# cnc-controller.net
KiCad netlist of a schematic drawn in EAGLE
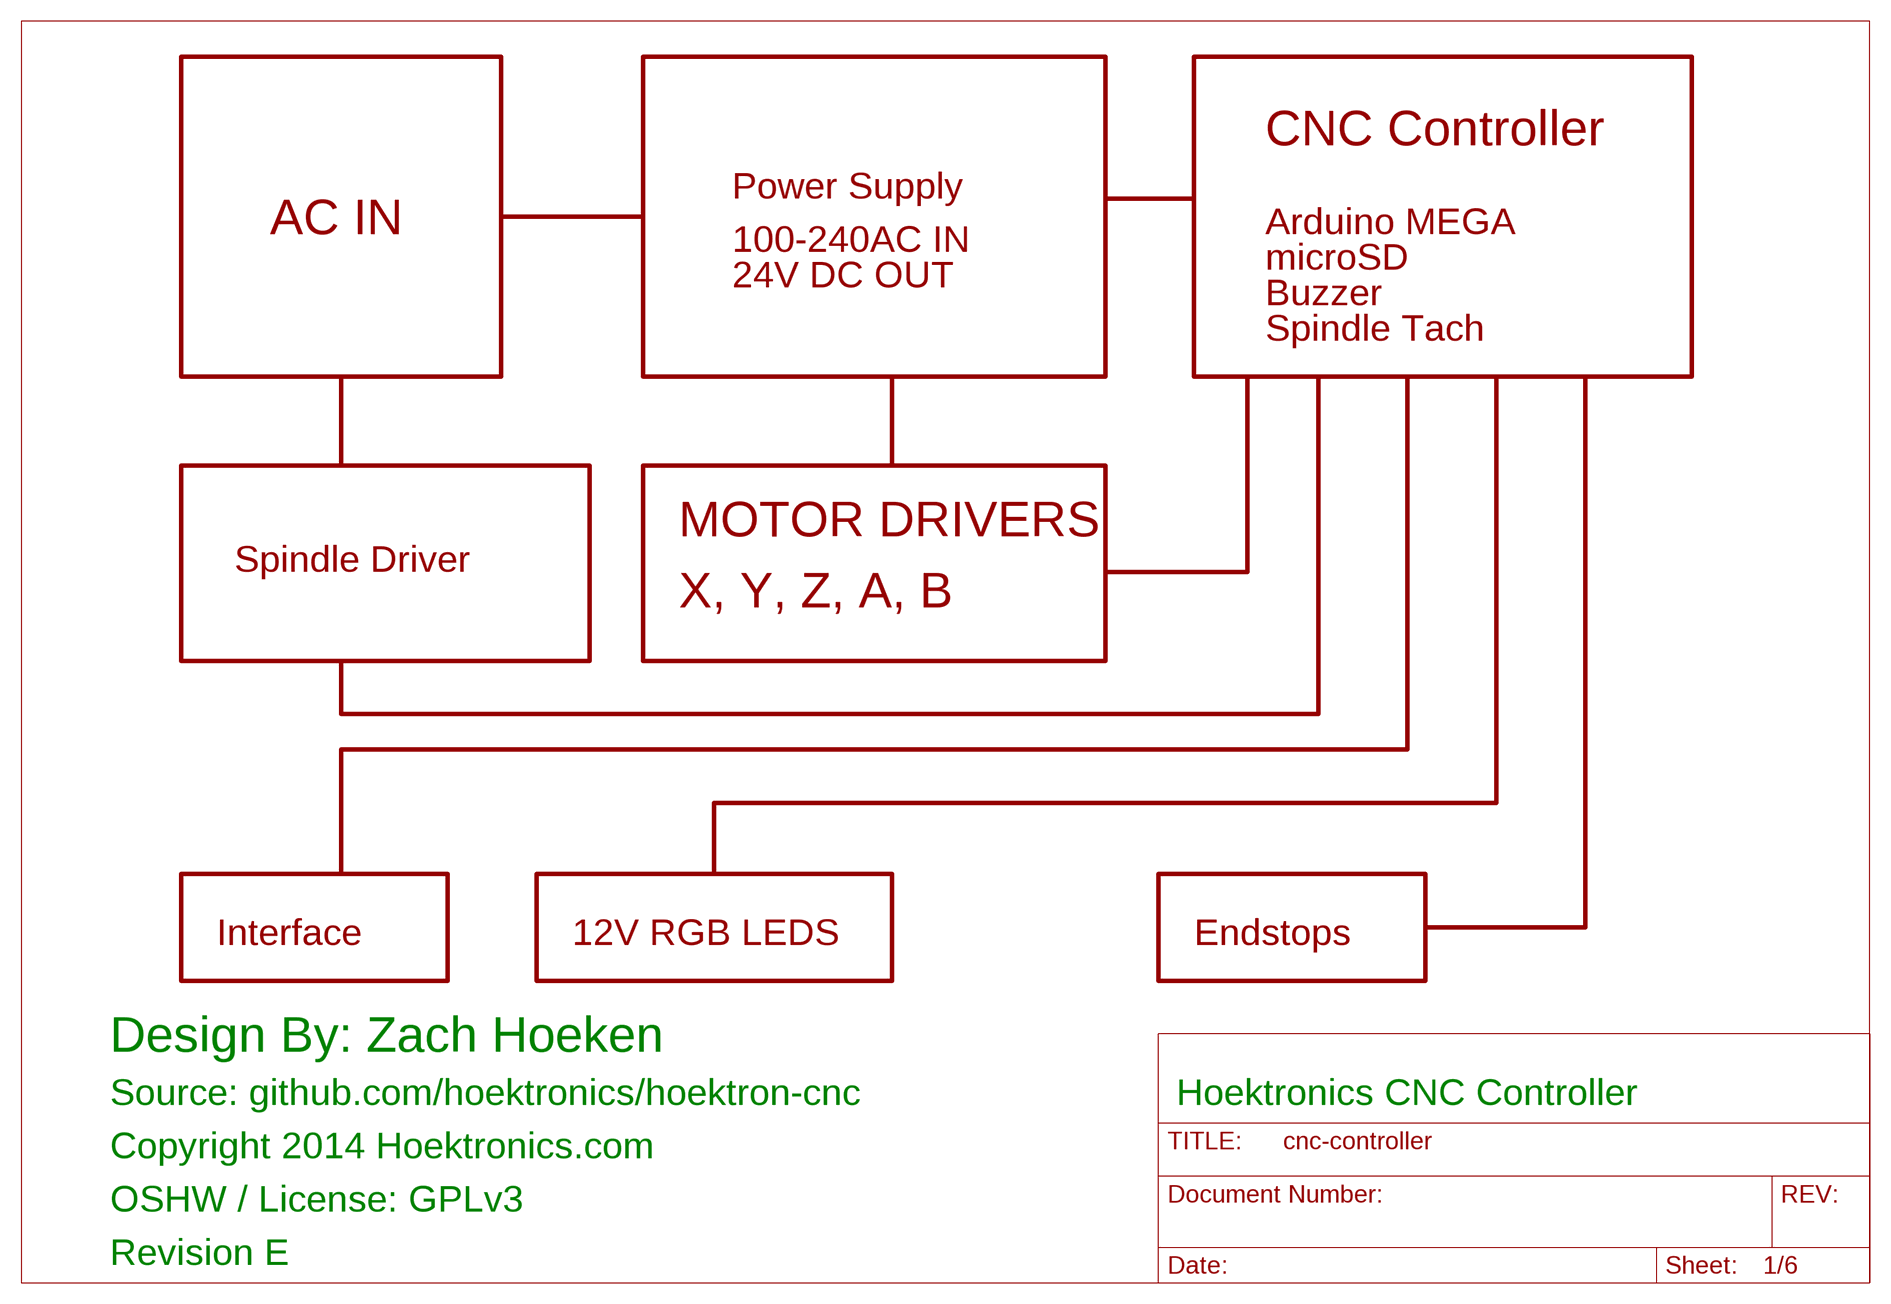
[diagram p0: schematic, sheet 1]
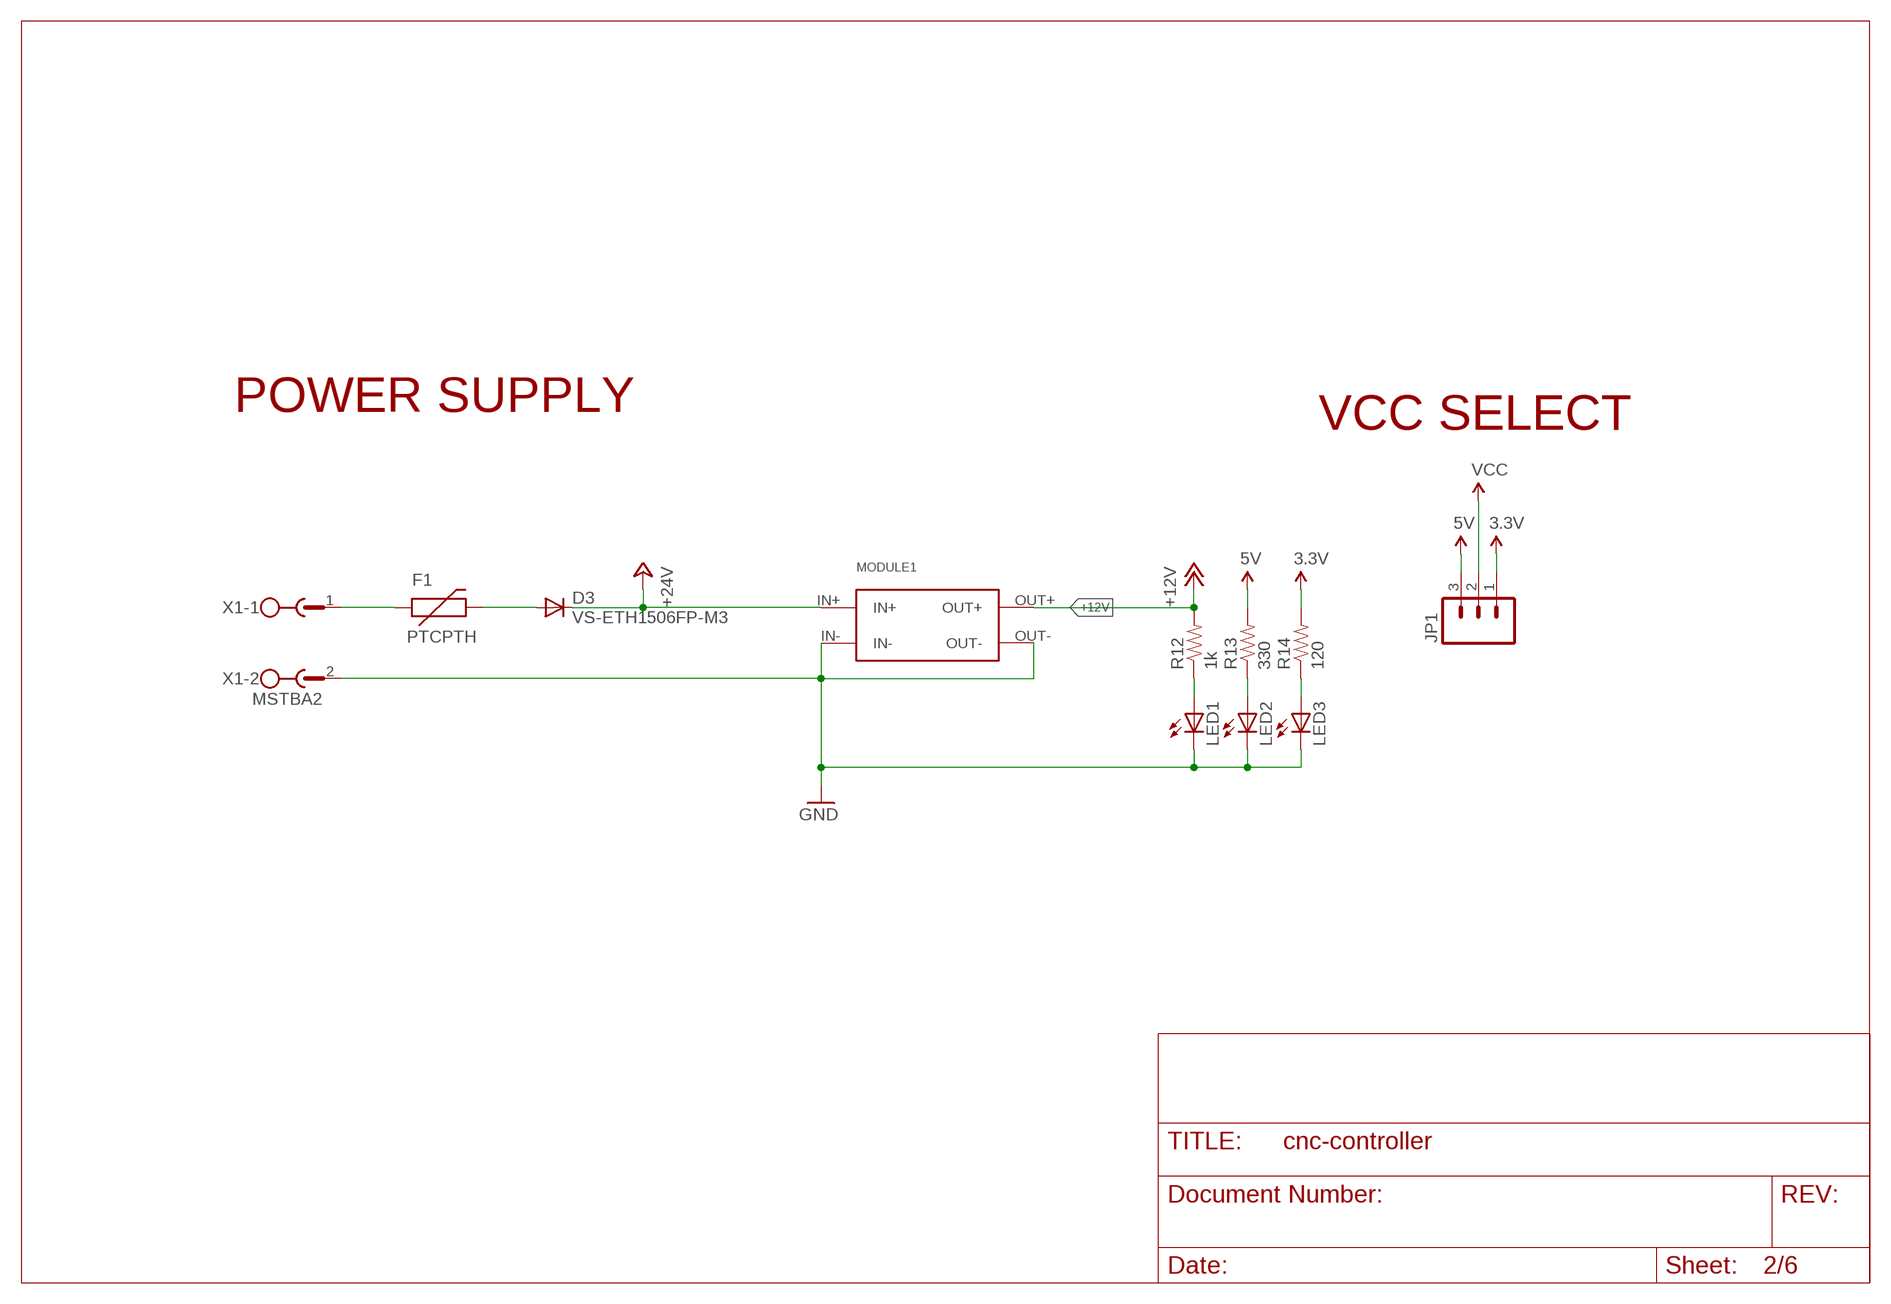
[diagram p1: schematic, sheet 2]
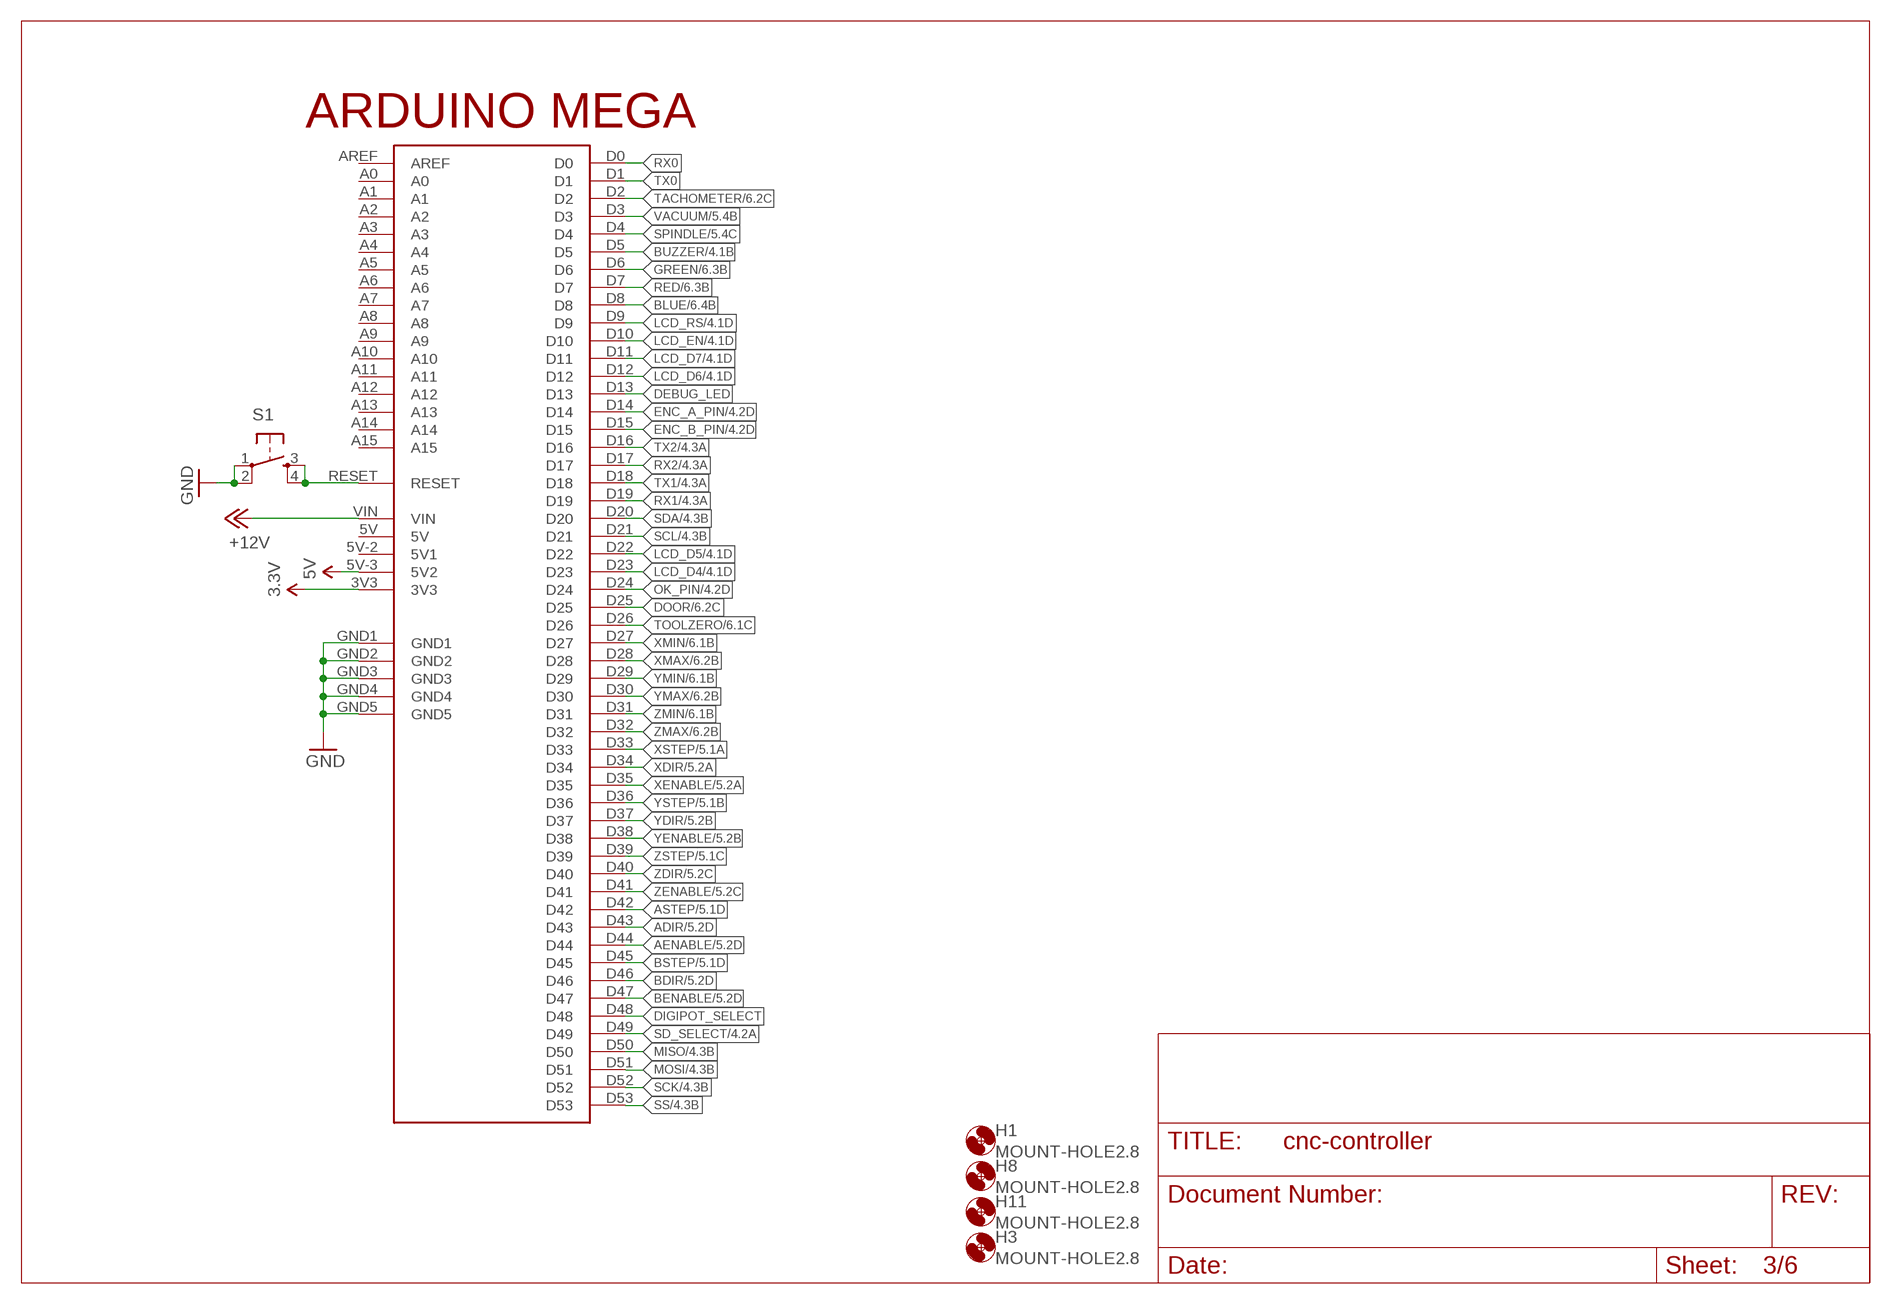
[diagram p2: schematic, sheet 3]
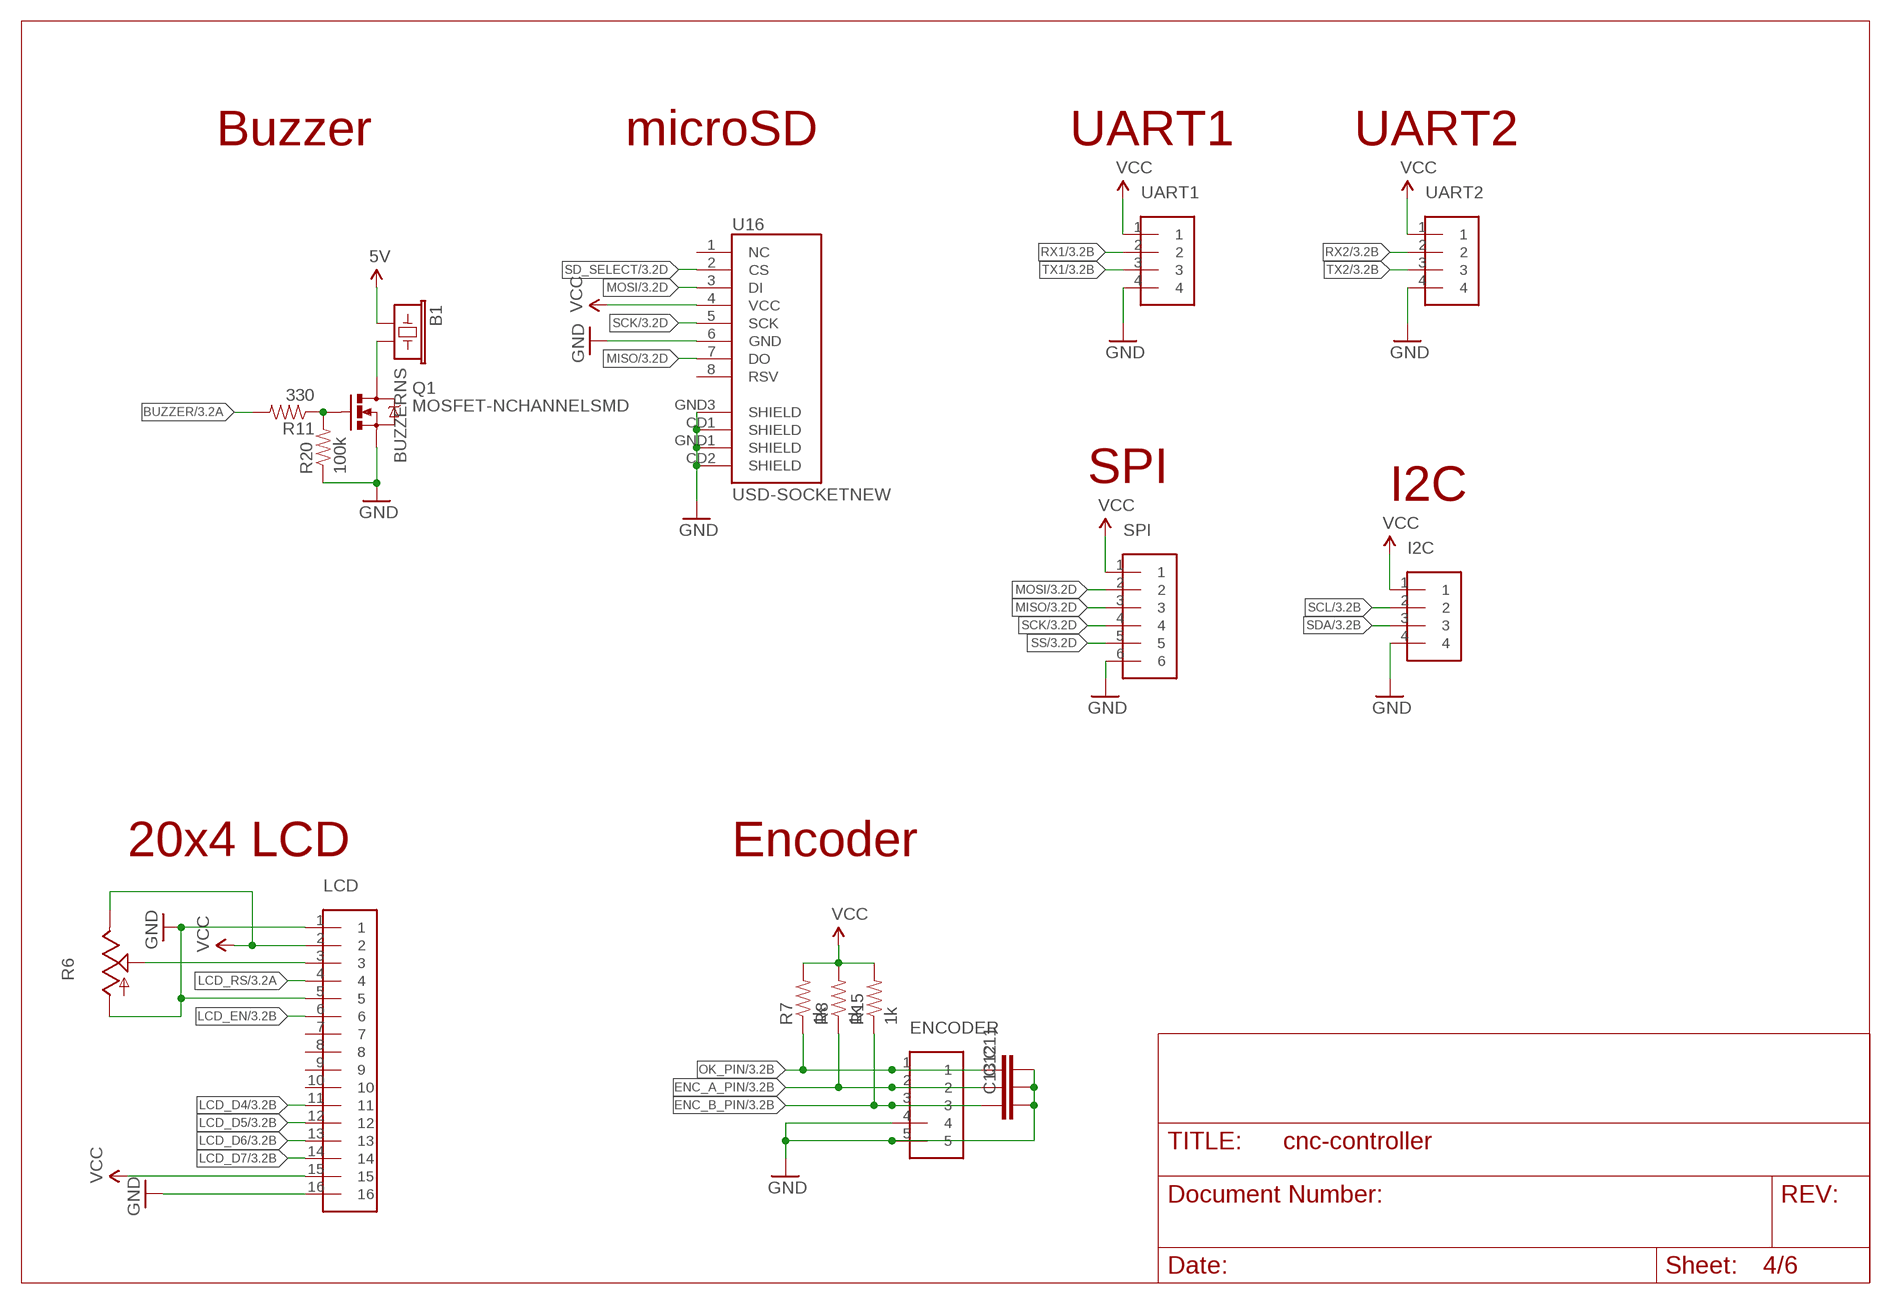
[diagram p3: schematic, sheet 4]
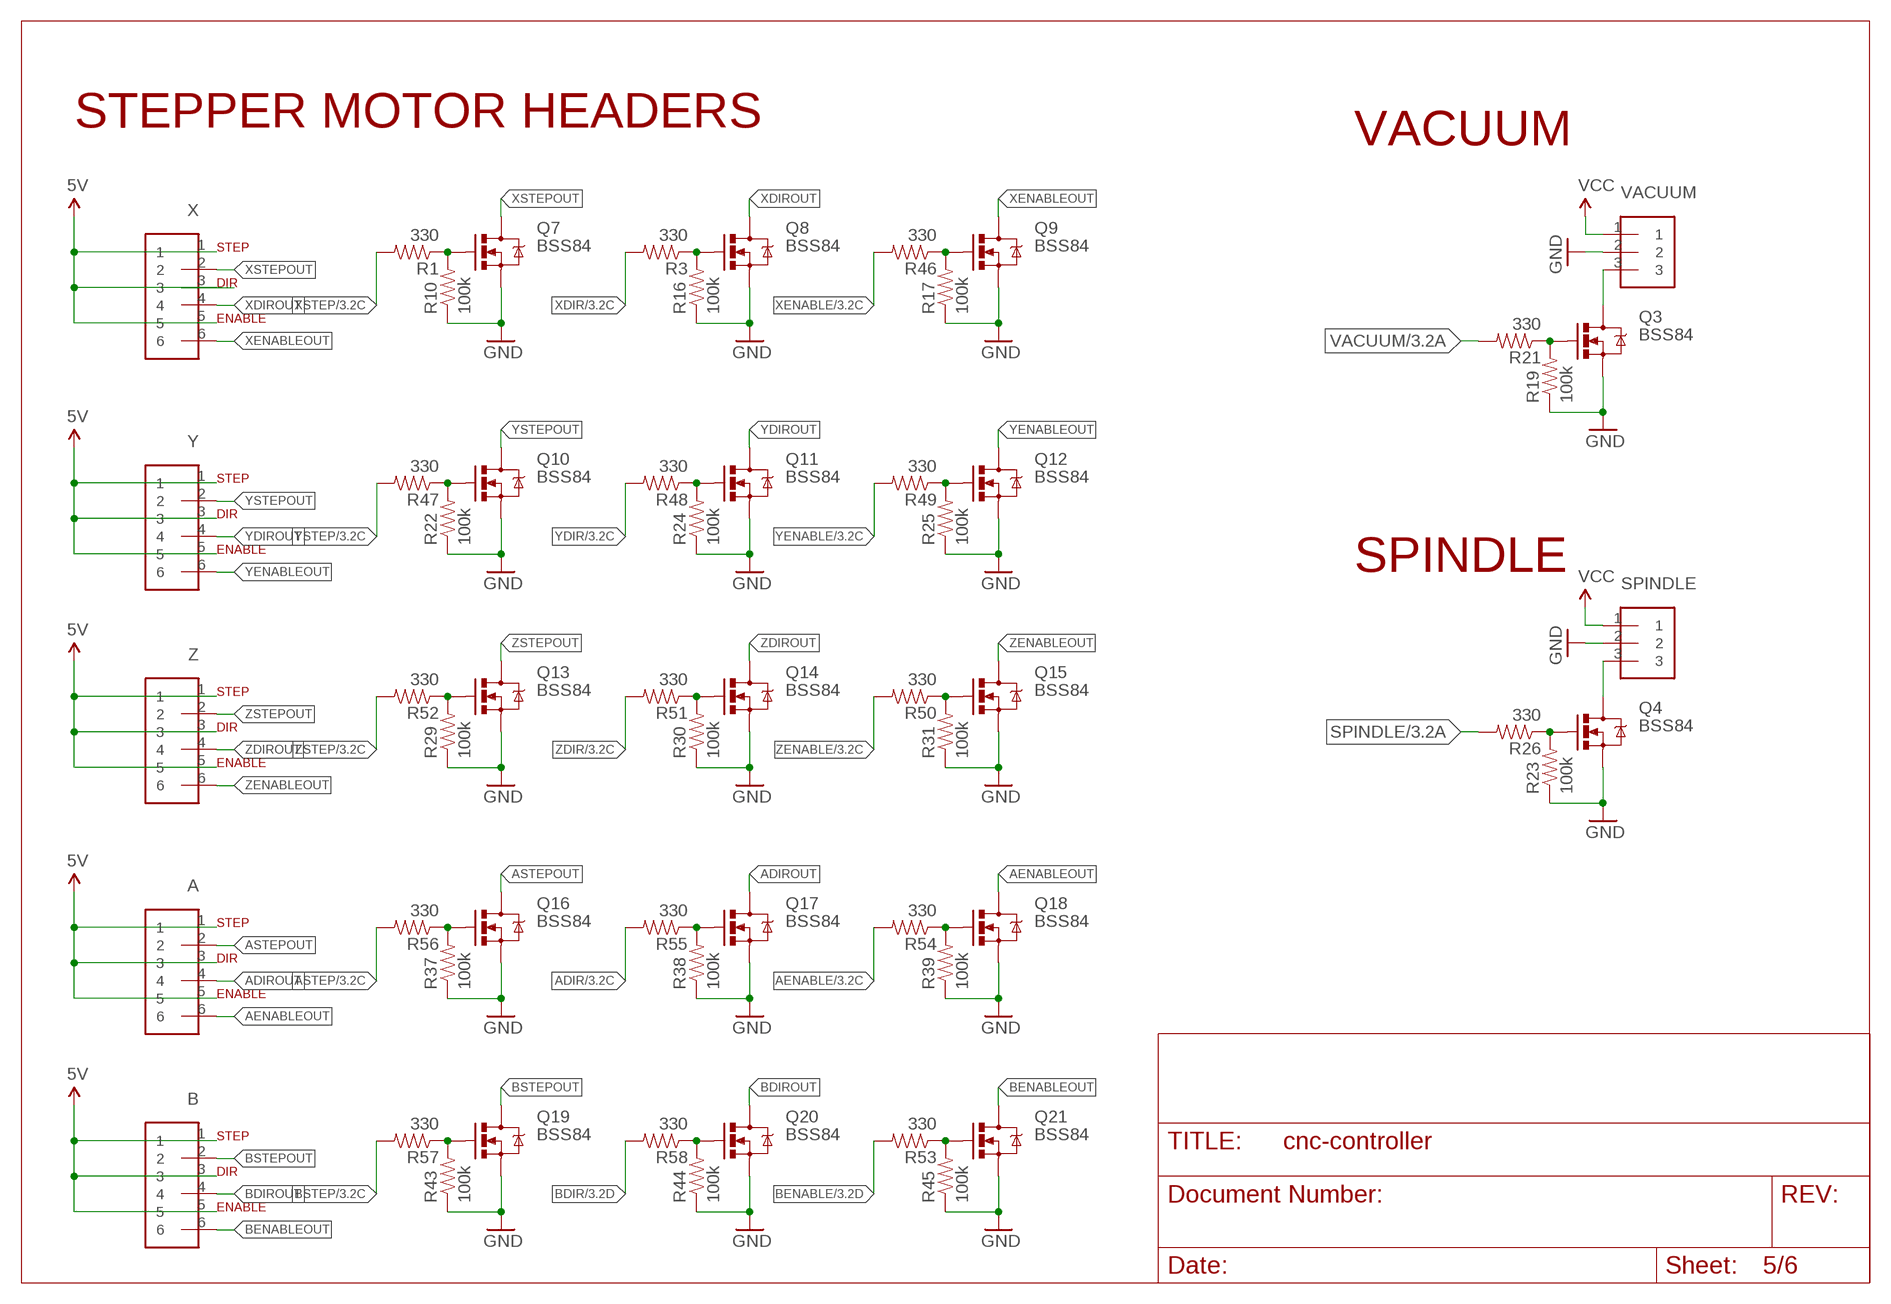
[diagram p4: schematic, sheet 5]
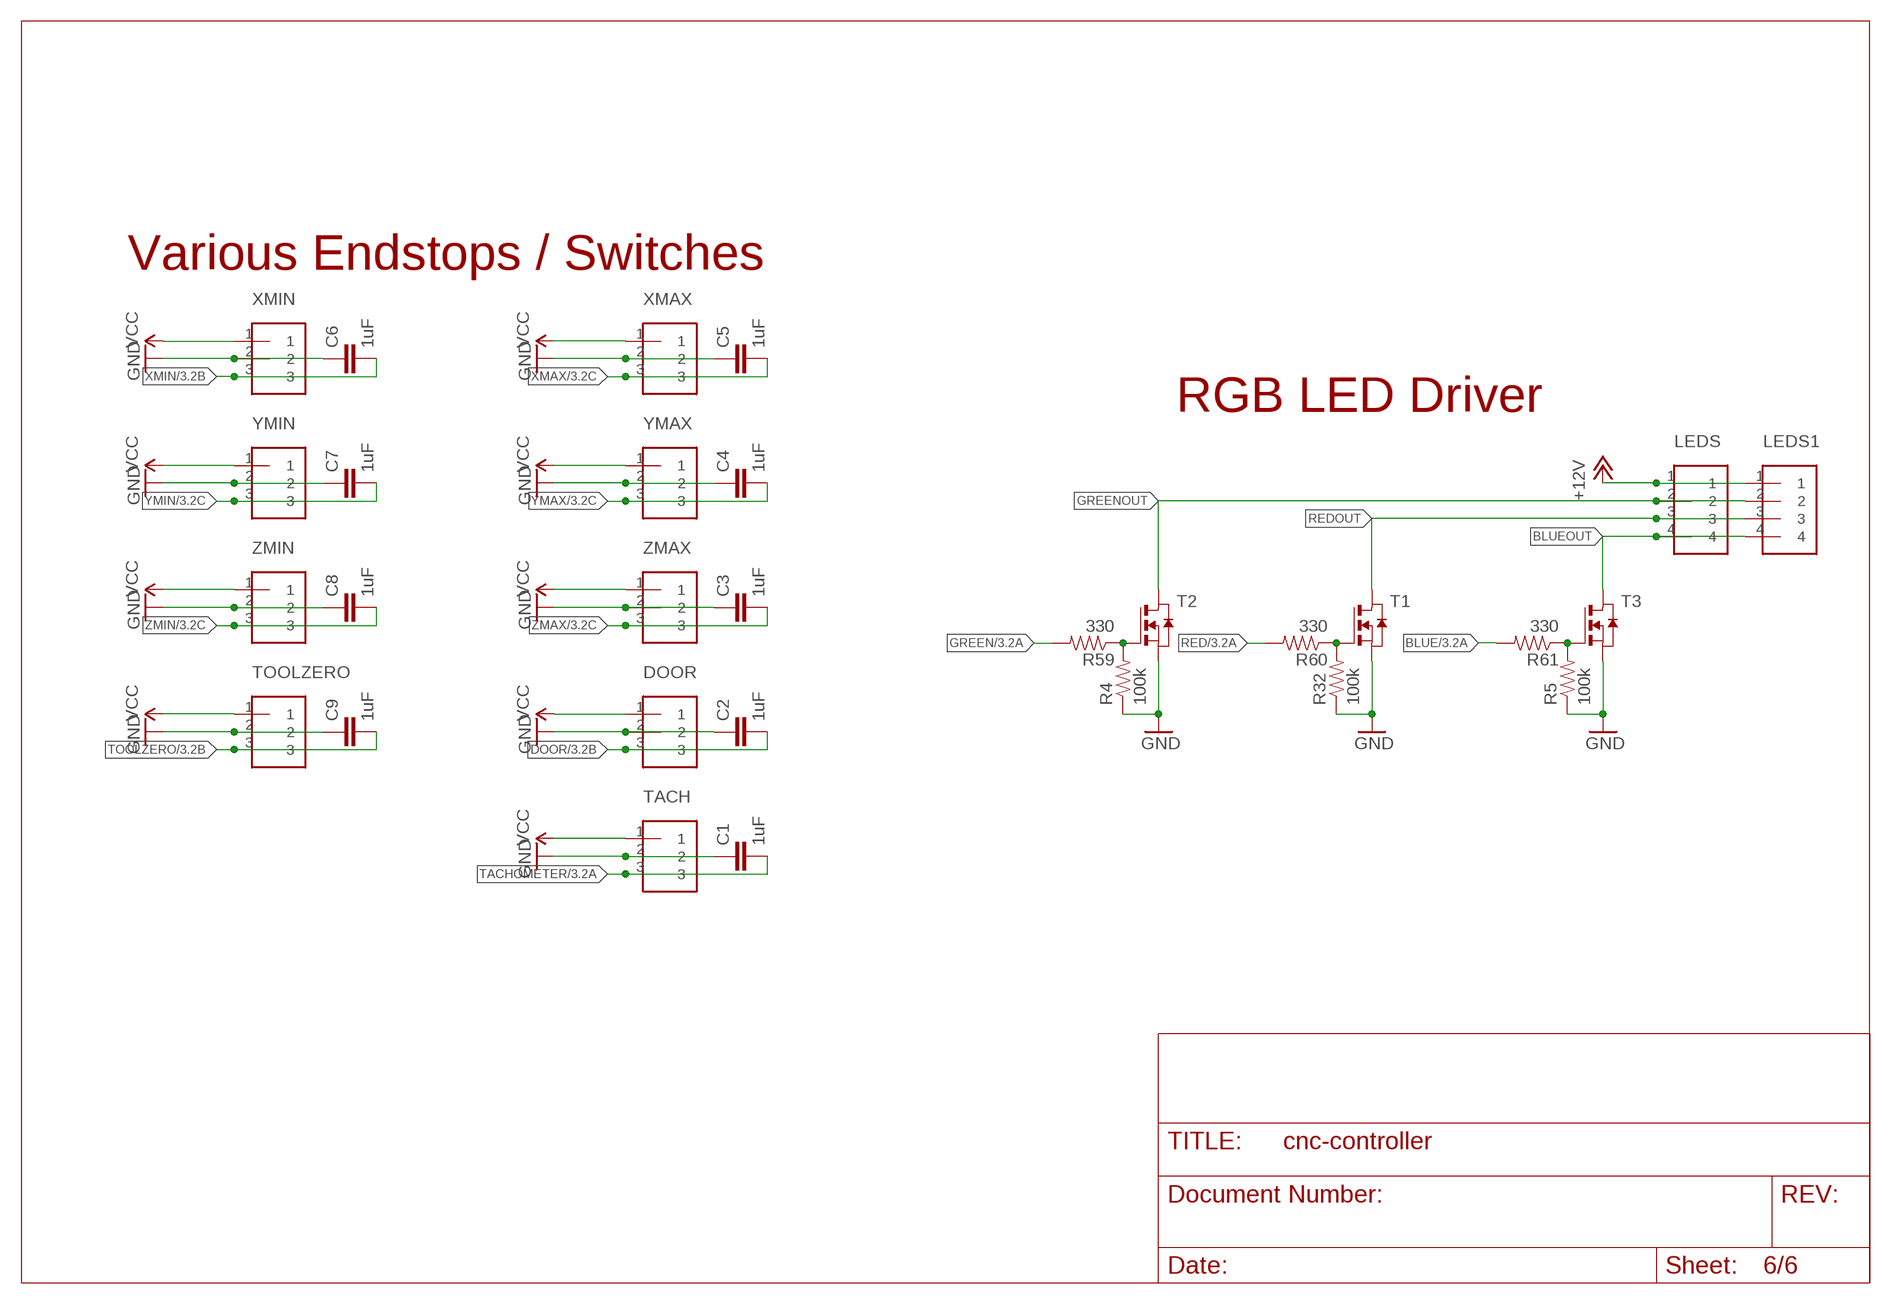
[diagram p5: schematic, sheet 6]

(export (version "E")
  (design (tool "Eeschema 10.0.6"))
  (components
    (comp (ref "C1")
      (value "1uF")
      (footprint "eagle-import:0603-RC")
      (libsource (lib "eagle-import") (part "CAPACITOR0603"))
    )
    (comp (ref "C2")
      (value "1uF")
      (footprint "eagle-import:0603-RC")
      (libsource (lib "eagle-import") (part "CAPACITOR0603"))
    )
    (comp (ref "C3")
      (value "1uF")
      (footprint "eagle-import:0603-RC")
      (libsource (lib "eagle-import") (part "CAPACITOR0603"))
    )
    (comp (ref "C4")
      (value "1uF")
      (footprint "eagle-import:0603-RC")
      (libsource (lib "eagle-import") (part "CAPACITOR0603"))
    )
    (comp (ref "C5")
      (value "1uF")
      (footprint "eagle-import:0603-RC")
      (libsource (lib "eagle-import") (part "CAPACITOR0603"))
    )
    (comp (ref "C6")
      (value "1uF")
      (footprint "eagle-import:0603-RC")
      (libsource (lib "eagle-import") (part "CAPACITOR0603"))
    )
    (comp (ref "C7")
      (value "1uF")
      (footprint "eagle-import:0603-RC")
      (libsource (lib "eagle-import") (part "CAPACITOR0603"))
    )
    (comp (ref "C8")
      (value "1uF")
      (footprint "eagle-import:0603-RC")
      (libsource (lib "eagle-import") (part "CAPACITOR0603"))
    )
    (comp (ref "C9")
      (value "1uF")
      (footprint "eagle-import:0603-RC")
      (libsource (lib "eagle-import") (part "CAPACITOR0603"))
    )
    (comp (ref "DOOR")
      (value "CONN-3XH-3")
      (footprint "eagle-import:XH-3")
      (libsource (lib "eagle-import") (part "CONN-3XH-3"))
    )
    (comp (ref "LEDS")
      (value "CONN-4")
      (footprint "eagle-import:XH-4")
      (libsource (lib "eagle-import") (part "CONN-4"))
    )
    (comp (ref "LEDS1")
      (value "CONN-4")
      (footprint "eagle-import:XH-4")
      (libsource (lib "eagle-import") (part "CONN-4"))
    )
    (comp (ref "R4")
      (value "100k")
      (footprint "eagle-import:0603-RC")
      (libsource (lib "eagle-import") (part "RESISTOR0603"))
    )
    (comp (ref "R5")
      (value "100k")
      (footprint "eagle-import:0603-RC")
      (libsource (lib "eagle-import") (part "RESISTOR0603"))
    )
    (comp (ref "R32")
      (value "100k")
      (footprint "eagle-import:0603-RC")
      (libsource (lib "eagle-import") (part "RESISTOR0603"))
    )
    (comp (ref "R59")
      (value "330")
      (footprint "eagle-import:0603-RC")
      (libsource (lib "eagle-import") (part "RESISTOR0603"))
    )
    (comp (ref "R60")
      (value "330")
      (footprint "eagle-import:0603-RC")
      (libsource (lib "eagle-import") (part "RESISTOR0603"))
    )
    (comp (ref "R61")
      (value "330")
      (footprint "eagle-import:0603-RC")
      (libsource (lib "eagle-import") (part "RESISTOR0603"))
    )
    (comp (ref "T1")
      (value "NMOSSOT89")
      (footprint "eagle-import:SOT89")
      (libsource (lib "eagle-import") (part "NMOSSOT89"))
    )
    (comp (ref "T2")
      (value "NMOSSOT89")
      (footprint "eagle-import:SOT89")
      (libsource (lib "eagle-import") (part "NMOSSOT89"))
    )
    (comp (ref "T3")
      (value "NMOSSOT89")
      (footprint "eagle-import:SOT89")
      (libsource (lib "eagle-import") (part "NMOSSOT89"))
    )
    (comp (ref "TACH")
      (value "CONN-3XH-3")
      (footprint "eagle-import:XH-3")
      (libsource (lib "eagle-import") (part "CONN-3XH-3"))
    )
    (comp (ref "TOOLZERO")
      (value "CONN-3XH-3")
      (footprint "eagle-import:XH-3")
      (libsource (lib "eagle-import") (part "CONN-3XH-3"))
    )
    (comp (ref "XMAX")
      (value "CONN-3XH-3")
      (footprint "eagle-import:XH-3")
      (libsource (lib "eagle-import") (part "CONN-3XH-3"))
    )
    (comp (ref "XMIN")
      (value "CONN-3XH-3")
      (footprint "eagle-import:XH-3")
      (libsource (lib "eagle-import") (part "CONN-3XH-3"))
    )
    (comp (ref "YMAX")
      (value "CONN-3XH-3")
      (footprint "eagle-import:XH-3")
      (libsource (lib "eagle-import") (part "CONN-3XH-3"))
    )
    (comp (ref "YMIN")
      (value "CONN-3XH-3")
      (footprint "eagle-import:XH-3")
      (libsource (lib "eagle-import") (part "CONN-3XH-3"))
    )
    (comp (ref "ZMAX")
      (value "CONN-3XH-3")
      (footprint "eagle-import:XH-3")
      (libsource (lib "eagle-import") (part "CONN-3XH-3"))
    )
    (comp (ref "ZMIN")
      (value "CONN-3XH-3")
      (footprint "eagle-import:XH-3")
      (libsource (lib "eagle-import") (part "CONN-3XH-3"))
    )
    (comp (ref "H1")
      (value "MOUNT-HOLE2.8")
      (footprint "eagle-import:2,8")
      (libsource (lib "eagle-import") (part "MOUNT-HOLE2.8"))
    )
    (comp (ref "H3")
      (value "MOUNT-HOLE2.8")
      (footprint "eagle-import:2,8")
      (libsource (lib "eagle-import") (part "MOUNT-HOLE2.8"))
    )
    (comp (ref "H8")
      (value "MOUNT-HOLE2.8")
      (footprint "eagle-import:2,8")
      (libsource (lib "eagle-import") (part "MOUNT-HOLE2.8"))
    )
    (comp (ref "H11")
      (value "MOUNT-HOLE2.8")
      (footprint "eagle-import:2,8")
      (libsource (lib "eagle-import") (part "MOUNT-HOLE2.8"))
    )
    (comp (ref "S1")
      (value "TAC_SWITCHSMD")
      (footprint "eagle-import:TACTILE_SWITCH_SMD")
      (libsource (lib "eagle-import") (part "TAC_SWITCHSMD"))
    )
    (comp (ref "U$1")
      (value "ARDUINO-MEGA")
      (footprint "eagle-import:ARDUINO-MEGA")
      (libsource (lib "eagle-import") (part "ARDUINO-MEGA"))
    )
    (comp (ref "D3")
      (value "VS-ETH1506FP-M3")
      (footprint "eagle-import:SMB")
      (libsource (lib "eagle-import") (part "DIODE-SMB"))
    )
    (comp (ref "F1")
      (value "PTCPTH")
      (footprint "eagle-import:PTC")
      (libsource (lib "eagle-import") (part "PTCPTH"))
    )
    (comp (ref "JP1")
      (value "M03PTH")
      (footprint "eagle-import:1X03")
      (libsource (lib "eagle-import") (part "M03PTH"))
    )
    (comp (ref "LED1")
      (value "LED0805")
      (footprint "eagle-import:0805-LED")
      (libsource (lib "eagle-import") (part "LED0805"))
    )
    (comp (ref "LED2")
      (value "LED0805")
      (footprint "eagle-import:0805-LED")
      (libsource (lib "eagle-import") (part "LED0805"))
    )
    (comp (ref "LED3")
      (value "LED0805")
      (footprint "eagle-import:0805-LED")
      (libsource (lib "eagle-import") (part "LED0805"))
    )
    (comp (ref "MODULE1")
      (value "DC-DC-CONVERTER")
      (footprint "eagle-import:DC-DC-MODULE")
      (libsource (lib "eagle-import") (part "DC-DC-CONVERTER"))
    )
    (comp (ref "R12")
      (value "1k")
      (footprint "eagle-import:0603-RC")
      (libsource (lib "eagle-import") (part "RESISTOR0603"))
    )
    (comp (ref "R13")
      (value "330")
      (footprint "eagle-import:0603-RC")
      (libsource (lib "eagle-import") (part "RESISTOR0603"))
    )
    (comp (ref "R14")
      (value "120")
      (footprint "eagle-import:0603-RC")
      (libsource (lib "eagle-import") (part "RESISTOR0603"))
    )
    (comp (ref "X1")
      (value "MSTBA2")
      (footprint "eagle-import:MSTBA2")
      (fields (field (name "MF") "FARNELL") (field (name "MPN") "1757242"))
      (libsource (lib "eagle-import") (part "MSTBA2"))
    )
    (comp (ref "A")
      (value "CONN-6")
      (footprint "eagle-import:XH-6")
      (libsource (lib "eagle-import") (part "CONN-6"))
    )
    (comp (ref "B")
      (value "CONN-6")
      (footprint "eagle-import:XH-6")
      (libsource (lib "eagle-import") (part "CONN-6"))
    )
    (comp (ref "Q3")
      (value "BSS84")
      (footprint "eagle-import:SOT23-3")
      (libsource (lib "eagle-import") (part "MOSFET-NCHANNELSMD"))
    )
    (comp (ref "Q4")
      (value "BSS84")
      (footprint "eagle-import:SOT23-3")
      (libsource (lib "eagle-import") (part "MOSFET-NCHANNELSMD"))
    )
    (comp (ref "Q7")
      (value "BSS84")
      (footprint "eagle-import:SOT23-3")
      (libsource (lib "eagle-import") (part "MOSFET-NCHANNELSMD"))
    )
    (comp (ref "Q8")
      (value "BSS84")
      (footprint "eagle-import:SOT23-3")
      (libsource (lib "eagle-import") (part "MOSFET-NCHANNELSMD"))
    )
    (comp (ref "Q9")
      (value "BSS84")
      (footprint "eagle-import:SOT23-3")
      (libsource (lib "eagle-import") (part "MOSFET-NCHANNELSMD"))
    )
    (comp (ref "Q10")
      (value "BSS84")
      (footprint "eagle-import:SOT23-3")
      (libsource (lib "eagle-import") (part "MOSFET-NCHANNELSMD"))
    )
    (comp (ref "Q11")
      (value "BSS84")
      (footprint "eagle-import:SOT23-3")
      (libsource (lib "eagle-import") (part "MOSFET-NCHANNELSMD"))
    )
    (comp (ref "Q12")
      (value "BSS84")
      (footprint "eagle-import:SOT23-3")
      (libsource (lib "eagle-import") (part "MOSFET-NCHANNELSMD"))
    )
    (comp (ref "Q13")
      (value "BSS84")
      (footprint "eagle-import:SOT23-3")
      (libsource (lib "eagle-import") (part "MOSFET-NCHANNELSMD"))
    )
    (comp (ref "Q14")
      (value "BSS84")
      (footprint "eagle-import:SOT23-3")
      (libsource (lib "eagle-import") (part "MOSFET-NCHANNELSMD"))
    )
    (comp (ref "Q15")
      (value "BSS84")
      (footprint "eagle-import:SOT23-3")
      (libsource (lib "eagle-import") (part "MOSFET-NCHANNELSMD"))
    )
    (comp (ref "Q16")
      (value "BSS84")
      (footprint "eagle-import:SOT23-3")
      (libsource (lib "eagle-import") (part "MOSFET-NCHANNELSMD"))
    )
    (comp (ref "Q17")
      (value "BSS84")
      (footprint "eagle-import:SOT23-3")
      (libsource (lib "eagle-import") (part "MOSFET-NCHANNELSMD"))
    )
    (comp (ref "Q18")
      (value "BSS84")
      (footprint "eagle-import:SOT23-3")
      (libsource (lib "eagle-import") (part "MOSFET-NCHANNELSMD"))
    )
    (comp (ref "Q19")
      (value "BSS84")
      (footprint "eagle-import:SOT23-3")
      (libsource (lib "eagle-import") (part "MOSFET-NCHANNELSMD"))
    )
    (comp (ref "Q20")
      (value "BSS84")
      (footprint "eagle-import:SOT23-3")
      (libsource (lib "eagle-import") (part "MOSFET-NCHANNELSMD"))
    )
    (comp (ref "Q21")
      (value "BSS84")
      (footprint "eagle-import:SOT23-3")
      (libsource (lib "eagle-import") (part "MOSFET-NCHANNELSMD"))
    )
    (comp (ref "R1")
      (value "330")
      (footprint "eagle-import:0603-RC")
      (libsource (lib "eagle-import") (part "RESISTOR0603"))
    )
    (comp (ref "R3")
      (value "330")
      (footprint "eagle-import:0603-RC")
      (libsource (lib "eagle-import") (part "RESISTOR0603"))
    )
    (comp (ref "R10")
      (value "100k")
      (footprint "eagle-import:0603-RC")
      (libsource (lib "eagle-import") (part "RESISTOR0603"))
    )
    (comp (ref "R16")
      (value "100k")
      (footprint "eagle-import:0603-RC")
      (libsource (lib "eagle-import") (part "RESISTOR0603"))
    )
    (comp (ref "R17")
      (value "100k")
      (footprint "eagle-import:0603-RC")
      (libsource (lib "eagle-import") (part "RESISTOR0603"))
    )
    (comp (ref "R19")
      (value "100k")
      (footprint "eagle-import:0603-RC")
      (libsource (lib "eagle-import") (part "RESISTOR0603"))
    )
    (comp (ref "R21")
      (value "330")
      (footprint "eagle-import:0603-RC")
      (libsource (lib "eagle-import") (part "RESISTOR0603"))
    )
    (comp (ref "R22")
      (value "100k")
      (footprint "eagle-import:0603-RC")
      (libsource (lib "eagle-import") (part "RESISTOR0603"))
    )
    (comp (ref "R23")
      (value "100k")
      (footprint "eagle-import:0603-RC")
      (libsource (lib "eagle-import") (part "RESISTOR0603"))
    )
    (comp (ref "R24")
      (value "100k")
      (footprint "eagle-import:0603-RC")
      (libsource (lib "eagle-import") (part "RESISTOR0603"))
    )
    (comp (ref "R25")
      (value "100k")
      (footprint "eagle-import:0603-RC")
      (libsource (lib "eagle-import") (part "RESISTOR0603"))
    )
    (comp (ref "R26")
      (value "330")
      (footprint "eagle-import:0603-RC")
      (libsource (lib "eagle-import") (part "RESISTOR0603"))
    )
    (comp (ref "R29")
      (value "100k")
      (footprint "eagle-import:0603-RC")
      (libsource (lib "eagle-import") (part "RESISTOR0603"))
    )
    (comp (ref "R30")
      (value "100k")
      (footprint "eagle-import:0603-RC")
      (libsource (lib "eagle-import") (part "RESISTOR0603"))
    )
    (comp (ref "R31")
      (value "100k")
      (footprint "eagle-import:0603-RC")
      (libsource (lib "eagle-import") (part "RESISTOR0603"))
    )
    (comp (ref "R37")
      (value "100k")
      (footprint "eagle-import:0603-RC")
      (libsource (lib "eagle-import") (part "RESISTOR0603"))
    )
    (comp (ref "R38")
      (value "100k")
      (footprint "eagle-import:0603-RC")
      (libsource (lib "eagle-import") (part "RESISTOR0603"))
    )
    (comp (ref "R39")
      (value "100k")
      (footprint "eagle-import:0603-RC")
      (libsource (lib "eagle-import") (part "RESISTOR0603"))
    )
    (comp (ref "R43")
      (value "100k")
      (footprint "eagle-import:0603-RC")
      (libsource (lib "eagle-import") (part "RESISTOR0603"))
    )
    (comp (ref "R44")
      (value "100k")
      (footprint "eagle-import:0603-RC")
      (libsource (lib "eagle-import") (part "RESISTOR0603"))
    )
    (comp (ref "R45")
      (value "100k")
      (footprint "eagle-import:0603-RC")
      (libsource (lib "eagle-import") (part "RESISTOR0603"))
    )
    (comp (ref "R46")
      (value "330")
      (footprint "eagle-import:0603-RC")
      (libsource (lib "eagle-import") (part "RESISTOR0603"))
    )
    (comp (ref "R47")
      (value "330")
      (footprint "eagle-import:0603-RC")
      (libsource (lib "eagle-import") (part "RESISTOR0603"))
    )
    (comp (ref "R48")
      (value "330")
      (footprint "eagle-import:0603-RC")
      (libsource (lib "eagle-import") (part "RESISTOR0603"))
    )
    (comp (ref "R49")
      (value "330")
      (footprint "eagle-import:0603-RC")
      (libsource (lib "eagle-import") (part "RESISTOR0603"))
    )
    (comp (ref "R50")
      (value "330")
      (footprint "eagle-import:0603-RC")
      (libsource (lib "eagle-import") (part "RESISTOR0603"))
    )
    (comp (ref "R51")
      (value "330")
      (footprint "eagle-import:0603-RC")
      (libsource (lib "eagle-import") (part "RESISTOR0603"))
    )
    (comp (ref "R52")
      (value "330")
      (footprint "eagle-import:0603-RC")
      (libsource (lib "eagle-import") (part "RESISTOR0603"))
    )
    (comp (ref "R53")
      (value "330")
      (footprint "eagle-import:0603-RC")
      (libsource (lib "eagle-import") (part "RESISTOR0603"))
    )
    (comp (ref "R54")
      (value "330")
      (footprint "eagle-import:0603-RC")
      (libsource (lib "eagle-import") (part "RESISTOR0603"))
    )
    (comp (ref "R55")
      (value "330")
      (footprint "eagle-import:0603-RC")
      (libsource (lib "eagle-import") (part "RESISTOR0603"))
    )
    (comp (ref "R56")
      (value "330")
      (footprint "eagle-import:0603-RC")
      (libsource (lib "eagle-import") (part "RESISTOR0603"))
    )
    (comp (ref "R57")
      (value "330")
      (footprint "eagle-import:0603-RC")
      (libsource (lib "eagle-import") (part "RESISTOR0603"))
    )
    (comp (ref "R58")
      (value "330")
      (footprint "eagle-import:0603-RC")
      (libsource (lib "eagle-import") (part "RESISTOR0603"))
    )
    (comp (ref "SPINDLE")
      (value "CONN-3XH-3")
      (footprint "eagle-import:XH-3")
      (libsource (lib "eagle-import") (part "CONN-3XH-3"))
    )
    (comp (ref "VACUUM")
      (value "CONN-3XH-3")
      (footprint "eagle-import:XH-3")
      (libsource (lib "eagle-import") (part "CONN-3XH-3"))
    )
    (comp (ref "X")
      (value "CONN-6")
      (footprint "eagle-import:XH-6")
      (libsource (lib "eagle-import") (part "CONN-6"))
    )
    (comp (ref "Y")
      (value "CONN-6")
      (footprint "eagle-import:XH-6")
      (libsource (lib "eagle-import") (part "CONN-6"))
    )
    (comp (ref "Z")
      (value "CONN-6")
      (footprint "eagle-import:XH-6")
      (libsource (lib "eagle-import") (part "CONN-6"))
    )
    (comp (ref "B1")
      (value "BUZZERNS")
      (footprint "eagle-import:BUZZER-12MM-NS")
      (libsource (lib "eagle-import") (part "BUZZERNS"))
    )
    (comp (ref "C11")
      (value "CAPACITOR0805")
      (footprint "eagle-import:0805-RC")
      (libsource (lib "eagle-import") (part "CAPACITOR0805"))
    )
    (comp (ref "C12")
      (value "CAPACITOR0805")
      (footprint "eagle-import:0805-RC")
      (libsource (lib "eagle-import") (part "CAPACITOR0805"))
    )
    (comp (ref "C13")
      (value "CAPACITOR0805")
      (footprint "eagle-import:0805-RC")
      (libsource (lib "eagle-import") (part "CAPACITOR0805"))
    )
    (comp (ref "ENCODER")
      (value "CONN-5")
      (footprint "eagle-import:XH-5")
      (libsource (lib "eagle-import") (part "CONN-5"))
    )
    (comp (ref "I2C")
      (value "CONN-4")
      (footprint "eagle-import:XH-4")
      (libsource (lib "eagle-import") (part "CONN-4"))
    )
    (comp (ref "LCD")
      (value "CONN-16")
      (footprint "eagle-import:XH-16")
      (libsource (lib "eagle-import") (part "CONN-16"))
    )
    (comp (ref "Q1")
      (value "MOSFET-NCHANNELSMD")
      (footprint "eagle-import:SOT23-3")
      (libsource (lib "eagle-import") (part "MOSFET-NCHANNELSMD"))
    )
    (comp (ref "R6")
      (value "TRIM_US-B25P")
      (footprint "eagle-import:B25P")
      (libsource (lib "eagle-import") (part "TRIM_US-B25P"))
    )
    (comp (ref "R7")
      (value "1k")
      (footprint "eagle-import:0805-RC")
      (libsource (lib "eagle-import") (part "RESISTOR0805"))
    )
    (comp (ref "R8")
      (value "1k")
      (footprint "eagle-import:0805-RC")
      (libsource (lib "eagle-import") (part "RESISTOR0805"))
    )
    (comp (ref "R11")
      (value "330")
      (footprint "eagle-import:0603-RC")
      (libsource (lib "eagle-import") (part "RESISTOR0603"))
    )
    (comp (ref "R15")
      (value "1k")
      (footprint "eagle-import:0805-RC")
      (libsource (lib "eagle-import") (part "RESISTOR0805"))
    )
    (comp (ref "R20")
      (value "100k")
      (footprint "eagle-import:0603-RC")
      (libsource (lib "eagle-import") (part "RESISTOR0603"))
    )
    (comp (ref "SPI")
      (value "CONN-6")
      (footprint "eagle-import:XH-6")
      (libsource (lib "eagle-import") (part "CONN-6"))
    )
    (comp (ref "U16")
      (value "USD-SOCKETNEW")
      (footprint "eagle-import:MICRO-SD-SOCKET-PP")
      (libsource (lib "eagle-import") (part "USD-SOCKETNEW"))
    )
    (comp (ref "UART1")
      (value "CONN-4")
      (footprint "eagle-import:XH-4")
      (libsource (lib "eagle-import") (part "CONN-4"))
    )
    (comp (ref "UART2")
      (value "CONN-4")
      (footprint "eagle-import:XH-4")
      (libsource (lib "eagle-import") (part "CONN-4"))
    )
  )
  (nets
    (net (code "1") (name "+12V") (class "Default")
      (node (ref "LEDS") (pin "1") (pinfunction "1_1") (pintype "bidirectional"))
      (node (ref "LEDS1") (pin "1") (pinfunction "1_1") (pintype "bidirectional"))
      (node (ref "MODULE1") (pin "OUT+") (pinfunction "OUT+_OUT+") (pintype "bidirectional"))
      (node (ref "R12") (pin "2") (pinfunction "2_2") (pintype "passive"))
      (node (ref "U$1") (pin "VIN") (pinfunction "VIN_VIN") (pintype "bidirectional"))
    )
    (net (code "2") (name "+24V") (class "Default")
      (node (ref "D3") (pin "C") (pinfunction "C_C") (pintype "passive"))
      (node (ref "MODULE1") (pin "IN+") (pinfunction "IN+_IN+") (pintype "bidirectional"))
    )
    (net (code "3") (name "3.3V") (class "Default")
      (node (ref "JP1") (pin "1") (pinfunction "1_1") (pintype "passive"))
      (node (ref "R14") (pin "2") (pinfunction "2_2") (pintype "passive"))
      (node (ref "U$1") (pin "3V3") (pinfunction "3V3_3V3") (pintype "bidirectional"))
    )
    (net (code "4") (name "5V") (class "Default")
      (node (ref "A") (pin "1") (pinfunction "1_1") (pintype "bidirectional"))
      (node (ref "A") (pin "3") (pinfunction "3_3") (pintype "bidirectional"))
      (node (ref "A") (pin "5") (pinfunction "5_5") (pintype "bidirectional"))
      (node (ref "B") (pin "1") (pinfunction "1_1") (pintype "bidirectional"))
      (node (ref "B") (pin "3") (pinfunction "3_3") (pintype "bidirectional"))
      (node (ref "B") (pin "5") (pinfunction "5_5") (pintype "bidirectional"))
      (node (ref "B1") (pin "+") (pinfunction "1_+") (pintype "passive"))
      (node (ref "JP1") (pin "3") (pinfunction "3_3") (pintype "passive"))
      (node (ref "R13") (pin "2") (pinfunction "2_2") (pintype "passive"))
      (node (ref "U$1") (pin "5V-3") (pinfunction "5V2_5V-3") (pintype "bidirectional"))
      (node (ref "X") (pin "1") (pinfunction "1_1") (pintype "bidirectional"))
      (node (ref "X") (pin "3") (pinfunction "3_3") (pintype "bidirectional"))
      (node (ref "X") (pin "5") (pinfunction "5_5") (pintype "bidirectional"))
      (node (ref "Y") (pin "1") (pinfunction "1_1") (pintype "bidirectional"))
      (node (ref "Y") (pin "3") (pinfunction "3_3") (pintype "bidirectional"))
      (node (ref "Y") (pin "5") (pinfunction "5_5") (pintype "bidirectional"))
      (node (ref "Z") (pin "1") (pinfunction "1_1") (pintype "bidirectional"))
      (node (ref "Z") (pin "3") (pinfunction "3_3") (pintype "bidirectional"))
      (node (ref "Z") (pin "5") (pinfunction "5_5") (pintype "bidirectional"))
    )
    (net (code "5") (name "ADIR") (class "Default")
      (node (ref "R55") (pin "2") (pinfunction "2_2") (pintype "passive"))
      (node (ref "U$1") (pin "D43") (pinfunction "D43_D43") (pintype "bidirectional"))
    )
    (net (code "6") (name "ADIROUT") (class "Default")
      (node (ref "A") (pin "4") (pinfunction "4_4") (pintype "bidirectional"))
      (node (ref "Q17") (pin "3") (pinfunction "D_3") (pintype "passive"))
    )
    (net (code "7") (name "AENABLE") (class "Default")
      (node (ref "R54") (pin "2") (pinfunction "2_2") (pintype "passive"))
      (node (ref "U$1") (pin "D44") (pinfunction "D44_D44") (pintype "bidirectional"))
    )
    (net (code "8") (name "AENABLEOUT") (class "Default")
      (node (ref "A") (pin "6") (pinfunction "6_6") (pintype "bidirectional"))
      (node (ref "Q18") (pin "3") (pinfunction "D_3") (pintype "passive"))
    )
    (net (code "9") (name "ASTEP") (class "Default")
      (node (ref "R56") (pin "2") (pinfunction "2_2") (pintype "passive"))
      (node (ref "U$1") (pin "D42") (pinfunction "D42_D42") (pintype "bidirectional"))
    )
    (net (code "10") (name "ASTEPOUT") (class "Default")
      (node (ref "A") (pin "2") (pinfunction "2_2") (pintype "bidirectional"))
      (node (ref "Q16") (pin "3") (pinfunction "D_3") (pintype "passive"))
    )
    (net (code "11") (name "BDIR") (class "Default")
      (node (ref "R58") (pin "2") (pinfunction "2_2") (pintype "passive"))
      (node (ref "U$1") (pin "D46") (pinfunction "D46_D46") (pintype "bidirectional"))
    )
    (net (code "12") (name "BDIROUT") (class "Default")
      (node (ref "B") (pin "4") (pinfunction "4_4") (pintype "bidirectional"))
      (node (ref "Q20") (pin "3") (pinfunction "D_3") (pintype "passive"))
    )
    (net (code "13") (name "BENABLE") (class "Default")
      (node (ref "R53") (pin "2") (pinfunction "2_2") (pintype "passive"))
      (node (ref "U$1") (pin "D47") (pinfunction "D47_D47") (pintype "bidirectional"))
    )
    (net (code "14") (name "BENABLEOUT") (class "Default")
      (node (ref "B") (pin "6") (pinfunction "6_6") (pintype "bidirectional"))
      (node (ref "Q21") (pin "3") (pinfunction "D_3") (pintype "passive"))
    )
    (net (code "15") (name "BLUE") (class "Default")
      (node (ref "R61") (pin "2") (pinfunction "2_2") (pintype "passive"))
      (node (ref "U$1") (pin "D8") (pinfunction "D8_D8") (pintype "bidirectional"))
    )
    (net (code "16") (name "BLUEOUT") (class "Default")
      (node (ref "LEDS") (pin "4") (pinfunction "4_4") (pintype "bidirectional"))
      (node (ref "LEDS1") (pin "4") (pinfunction "4_4") (pintype "bidirectional"))
      (node (ref "T3") (pin "2") (pinfunction "D_2") (pintype "passive"))
    )
    (net (code "17") (name "BSTEP") (class "Default")
      (node (ref "R57") (pin "2") (pinfunction "2_2") (pintype "passive"))
      (node (ref "U$1") (pin "D45") (pinfunction "D45_D45") (pintype "bidirectional"))
    )
    (net (code "18") (name "BSTEPOUT") (class "Default")
      (node (ref "B") (pin "2") (pinfunction "2_2") (pintype "bidirectional"))
      (node (ref "Q19") (pin "3") (pinfunction "D_3") (pintype "passive"))
    )
    (net (code "19") (name "BUZZER") (class "Default")
      (node (ref "R11") (pin "2") (pinfunction "2_2") (pintype "passive"))
      (node (ref "U$1") (pin "D5") (pinfunction "D5_D5") (pintype "bidirectional"))
    )
    (net (code "20") (name "DEBUG_LED") (class "Default")
      (node (ref "U$1") (pin "D13") (pinfunction "D13_D13") (pintype "bidirectional"))
    )
    (net (code "21") (name "DIGIPOT_SELECT") (class "Default")
      (node (ref "U$1") (pin "D48") (pinfunction "D48_D48") (pintype "bidirectional"))
    )
    (net (code "22") (name "DOOR") (class "Default")
      (node (ref "C2") (pin "2") (pinfunction "2_2") (pintype "passive"))
      (node (ref "DOOR") (pin "3") (pinfunction "3_3") (pintype "bidirectional"))
      (node (ref "U$1") (pin "D25") (pinfunction "D25_D25") (pintype "bidirectional"))
    )
    (net (code "23") (name "ENC_A_PIN") (class "Default")
      (node (ref "C12") (pin "1") (pinfunction "1_1") (pintype "passive"))
      (node (ref "ENCODER") (pin "2") (pinfunction "2_2") (pintype "bidirectional"))
      (node (ref "R8") (pin "1") (pinfunction "1_1") (pintype "passive"))
      (node (ref "U$1") (pin "D14") (pinfunction "D14_D14") (pintype "bidirectional"))
    )
    (net (code "24") (name "ENC_B_PIN") (class "Default")
      (node (ref "C13") (pin "1") (pinfunction "1_1") (pintype "passive"))
      (node (ref "ENCODER") (pin "3") (pinfunction "3_3") (pintype "bidirectional"))
      (node (ref "R15") (pin "1") (pinfunction "1_1") (pintype "passive"))
      (node (ref "U$1") (pin "D15") (pinfunction "D15_D15") (pintype "bidirectional"))
    )
    (net (code "25") (name "GND") (class "Default")
      (node (ref "C1") (pin "1") (pinfunction "1_1") (pintype "passive"))
      (node (ref "C11") (pin "2") (pinfunction "2_2") (pintype "passive"))
      (node (ref "C12") (pin "2") (pinfunction "2_2") (pintype "passive"))
      (node (ref "C13") (pin "2") (pinfunction "2_2") (pintype "passive"))
      (node (ref "C2") (pin "1") (pinfunction "1_1") (pintype "passive"))
      (node (ref "C3") (pin "1") (pinfunction "1_1") (pintype "passive"))
      (node (ref "C4") (pin "1") (pinfunction "1_1") (pintype "passive"))
      (node (ref "C5") (pin "1") (pinfunction "1_1") (pintype "passive"))
      (node (ref "C6") (pin "1") (pinfunction "1_1") (pintype "passive"))
      (node (ref "C7") (pin "1") (pinfunction "1_1") (pintype "passive"))
      (node (ref "C8") (pin "1") (pinfunction "1_1") (pintype "passive"))
      (node (ref "C9") (pin "1") (pinfunction "1_1") (pintype "passive"))
      (node (ref "DOOR") (pin "2") (pinfunction "2_2") (pintype "bidirectional"))
      (node (ref "ENCODER") (pin "4") (pinfunction "4_4") (pintype "bidirectional"))
      (node (ref "ENCODER") (pin "5") (pinfunction "5_5") (pintype "bidirectional"))
      (node (ref "I2C") (pin "4") (pinfunction "4_4") (pintype "bidirectional"))
      (node (ref "LCD") (pin "1") (pinfunction "1_1") (pintype "bidirectional"))
      (node (ref "LCD") (pin "16") (pinfunction "16_16") (pintype "bidirectional"))
      (node (ref "LCD") (pin "5") (pinfunction "5_5") (pintype "bidirectional"))
      (node (ref "LED1") (pin "C") (pinfunction "C_C") (pintype "passive"))
      (node (ref "LED2") (pin "C") (pinfunction "C_C") (pintype "passive"))
      (node (ref "LED3") (pin "C") (pinfunction "C_C") (pintype "passive"))
      (node (ref "MODULE1") (pin "IN-") (pinfunction "IN-_IN-") (pintype "bidirectional"))
      (node (ref "MODULE1") (pin "OUT-") (pinfunction "OUT-_OUT-") (pintype "bidirectional"))
      (node (ref "Q1") (pin "2") (pinfunction "S_2") (pintype "passive"))
      (node (ref "Q10") (pin "2") (pinfunction "S_2") (pintype "passive"))
      (node (ref "Q11") (pin "2") (pinfunction "S_2") (pintype "passive"))
      (node (ref "Q12") (pin "2") (pinfunction "S_2") (pintype "passive"))
      (node (ref "Q13") (pin "2") (pinfunction "S_2") (pintype "passive"))
      (node (ref "Q14") (pin "2") (pinfunction "S_2") (pintype "passive"))
      (node (ref "Q15") (pin "2") (pinfunction "S_2") (pintype "passive"))
      (node (ref "Q16") (pin "2") (pinfunction "S_2") (pintype "passive"))
      (node (ref "Q17") (pin "2") (pinfunction "S_2") (pintype "passive"))
      (node (ref "Q18") (pin "2") (pinfunction "S_2") (pintype "passive"))
      (node (ref "Q19") (pin "2") (pinfunction "S_2") (pintype "passive"))
      (node (ref "Q20") (pin "2") (pinfunction "S_2") (pintype "passive"))
      (node (ref "Q21") (pin "2") (pinfunction "S_2") (pintype "passive"))
      (node (ref "Q3") (pin "2") (pinfunction "S_2") (pintype "passive"))
      (node (ref "Q4") (pin "2") (pinfunction "S_2") (pintype "passive"))
      (node (ref "Q7") (pin "2") (pinfunction "S_2") (pintype "passive"))
      (node (ref "Q8") (pin "2") (pinfunction "S_2") (pintype "passive"))
      (node (ref "Q9") (pin "2") (pinfunction "S_2") (pintype "passive"))
      (node (ref "R10") (pin "1") (pinfunction "1_1") (pintype "passive"))
      (node (ref "R16") (pin "1") (pinfunction "1_1") (pintype "passive"))
      (node (ref "R17") (pin "1") (pinfunction "1_1") (pintype "passive"))
      (node (ref "R19") (pin "1") (pinfunction "1_1") (pintype "passive"))
      (node (ref "R20") (pin "1") (pinfunction "1_1") (pintype "passive"))
      (node (ref "R22") (pin "1") (pinfunction "1_1") (pintype "passive"))
      (node (ref "R23") (pin "1") (pinfunction "1_1") (pintype "passive"))
      (node (ref "R24") (pin "1") (pinfunction "1_1") (pintype "passive"))
      (node (ref "R25") (pin "1") (pinfunction "1_1") (pintype "passive"))
      (node (ref "R29") (pin "1") (pinfunction "1_1") (pintype "passive"))
      (node (ref "R30") (pin "1") (pinfunction "1_1") (pintype "passive"))
      (node (ref "R31") (pin "1") (pinfunction "1_1") (pintype "passive"))
      (node (ref "R32") (pin "1") (pinfunction "1_1") (pintype "passive"))
      (node (ref "R37") (pin "1") (pinfunction "1_1") (pintype "passive"))
      (node (ref "R38") (pin "1") (pinfunction "1_1") (pintype "passive"))
      (node (ref "R39") (pin "1") (pinfunction "1_1") (pintype "passive"))
      (node (ref "R4") (pin "1") (pinfunction "1_1") (pintype "passive"))
      (node (ref "R43") (pin "1") (pinfunction "1_1") (pintype "passive"))
      (node (ref "R44") (pin "1") (pinfunction "1_1") (pintype "passive"))
      (node (ref "R45") (pin "1") (pinfunction "1_1") (pintype "passive"))
      (node (ref "R5") (pin "1") (pinfunction "1_1") (pintype "passive"))
      (node (ref "R6") (pin "A") (pinfunction "A_A") (pintype "passive"))
      (node (ref "S1") (pin "1") (pinfunction "1_1") (pintype "passive"))
      (node (ref "S1") (pin "2") (pinfunction "2_2") (pintype "passive"))
      (node (ref "SPI") (pin "6") (pinfunction "6_6") (pintype "bidirectional"))
      (node (ref "SPINDLE") (pin "2") (pinfunction "2_2") (pintype "bidirectional"))
      (node (ref "T1") (pin "3") (pinfunction "S_3") (pintype "passive"))
      (node (ref "T2") (pin "3") (pinfunction "S_3") (pintype "passive"))
      (node (ref "T3") (pin "3") (pinfunction "S_3") (pintype "passive"))
      (node (ref "TACH") (pin "2") (pinfunction "2_2") (pintype "bidirectional"))
      (node (ref "TOOLZERO") (pin "2") (pinfunction "2_2") (pintype "bidirectional"))
      (node (ref "U$1") (pin "GND1") (pinfunction "GND1_GND1") (pintype "bidirectional"))
      (node (ref "U$1") (pin "GND2") (pinfunction "GND2_GND2") (pintype "bidirectional"))
      (node (ref "U$1") (pin "GND3") (pinfunction "GND3_GND3") (pintype "bidirectional"))
      (node (ref "U$1") (pin "GND4") (pinfunction "GND4_GND4") (pintype "bidirectional"))
      (node (ref "U$1") (pin "GND5") (pinfunction "GND5_GND5") (pintype "bidirectional"))
      (node (ref "U16") (pin "6") (pinfunction "GND_6") (pintype "bidirectional"))
      (node (ref "U16") (pin "CD1") (pinfunction "SHIELD_CD1") (pintype "bidirectional"))
      (node (ref "U16") (pin "CD2") (pinfunction "SHIELD_CD2") (pintype "bidirectional"))
      (node (ref "U16") (pin "GND1") (pinfunction "SHIELD_GND1") (pintype "bidirectional"))
      (node (ref "U16") (pin "GND3") (pinfunction "SHIELD_GND3") (pintype "bidirectional"))
      (node (ref "UART1") (pin "4") (pinfunction "4_4") (pintype "bidirectional"))
      (node (ref "UART2") (pin "4") (pinfunction "4_4") (pintype "bidirectional"))
      (node (ref "VACUUM") (pin "2") (pinfunction "2_2") (pintype "bidirectional"))
      (node (ref "X1") (pin "2") (pinfunction "1_2") (pintype "passive"))
      (node (ref "XMAX") (pin "2") (pinfunction "2_2") (pintype "bidirectional"))
      (node (ref "XMIN") (pin "2") (pinfunction "2_2") (pintype "bidirectional"))
      (node (ref "YMAX") (pin "2") (pinfunction "2_2") (pintype "bidirectional"))
      (node (ref "YMIN") (pin "2") (pinfunction "2_2") (pintype "bidirectional"))
      (node (ref "ZMAX") (pin "2") (pinfunction "2_2") (pintype "bidirectional"))
      (node (ref "ZMIN") (pin "2") (pinfunction "2_2") (pintype "bidirectional"))
    )
    (net (code "26") (name "GREEN") (class "Default")
      (node (ref "R59") (pin "2") (pinfunction "2_2") (pintype "passive"))
      (node (ref "U$1") (pin "D6") (pinfunction "D6_D6") (pintype "bidirectional"))
    )
    (net (code "27") (name "GREENOUT") (class "Default")
      (node (ref "LEDS") (pin "2") (pinfunction "2_2") (pintype "bidirectional"))
      (node (ref "LEDS1") (pin "2") (pinfunction "2_2") (pintype "bidirectional"))
      (node (ref "T2") (pin "2") (pinfunction "D_2") (pintype "passive"))
    )
    (net (code "28") (name "LCD_D4") (class "Default")
      (node (ref "LCD") (pin "11") (pinfunction "11_11") (pintype "bidirectional"))
      (node (ref "U$1") (pin "D23") (pinfunction "D23_D23") (pintype "bidirectional"))
    )
    (net (code "29") (name "LCD_D5") (class "Default")
      (node (ref "LCD") (pin "12") (pinfunction "12_12") (pintype "bidirectional"))
      (node (ref "U$1") (pin "D22") (pinfunction "D22_D22") (pintype "bidirectional"))
    )
    (net (code "30") (name "LCD_D6") (class "Default")
      (node (ref "LCD") (pin "13") (pinfunction "13_13") (pintype "bidirectional"))
      (node (ref "U$1") (pin "D12") (pinfunction "D12_D12") (pintype "bidirectional"))
    )
    (net (code "31") (name "LCD_D7") (class "Default")
      (node (ref "LCD") (pin "14") (pinfunction "14_14") (pintype "bidirectional"))
      (node (ref "U$1") (pin "D11") (pinfunction "D11_D11") (pintype "bidirectional"))
    )
    (net (code "32") (name "LCD_EN") (class "Default")
      (node (ref "LCD") (pin "6") (pinfunction "6_6") (pintype "bidirectional"))
      (node (ref "U$1") (pin "D10") (pinfunction "D10_D10") (pintype "bidirectional"))
    )
    (net (code "33") (name "LCD_RS") (class "Default")
      (node (ref "LCD") (pin "4") (pinfunction "4_4") (pintype "bidirectional"))
      (node (ref "U$1") (pin "D9") (pinfunction "D9_D9") (pintype "bidirectional"))
    )
    (net (code "34") (name "MISO") (class "Default")
      (node (ref "SPI") (pin "3") (pinfunction "3_3") (pintype "bidirectional"))
      (node (ref "U$1") (pin "D50") (pinfunction "D50_D50") (pintype "bidirectional"))
      (node (ref "U16") (pin "7") (pinfunction "DO_7") (pintype "bidirectional"))
    )
    (net (code "35") (name "MOSI") (class "Default")
      (node (ref "SPI") (pin "2") (pinfunction "2_2") (pintype "bidirectional"))
      (node (ref "U$1") (pin "D51") (pinfunction "D51_D51") (pintype "bidirectional"))
      (node (ref "U16") (pin "3") (pinfunction "DI_3") (pintype "bidirectional"))
    )
    (net (code "36") (name "Net-(B1-2)") (class "Default")
      (node (ref "B1") (pin "-") (pinfunction "2_-") (pintype "passive"))
      (node (ref "Q1") (pin "3") (pinfunction "D_3") (pintype "passive"))
    )
    (net (code "37") (name "Net-(F1-1)") (class "Default")
      (node (ref "F1") (pin "P$1") (pinfunction "1_P$1") (pintype "bidirectional"))
      (node (ref "X1") (pin "1") (pinfunction "1_1") (pintype "passive"))
    )
    (net (code "38") (name "Net-(F1-2)") (class "Default")
      (node (ref "D3") (pin "A") (pinfunction "A_A") (pintype "passive"))
      (node (ref "F1") (pin "P$2") (pinfunction "2_P$2") (pintype "bidirectional"))
    )
    (net (code "39") (name "Net-(LCD-Pad3)") (class "Default")
      (node (ref "LCD") (pin "3") (pinfunction "3_3") (pintype "bidirectional"))
      (node (ref "R6") (pin "S") (pinfunction "S_S") (pintype "passive"))
    )
    (net (code "40") (name "Net-(LED1-PadA)") (class "Default")
      (node (ref "LED1") (pin "A") (pinfunction "A_A") (pintype "passive"))
      (node (ref "R12") (pin "1") (pinfunction "1_1") (pintype "passive"))
    )
    (net (code "41") (name "Net-(LED2-PadA)") (class "Default")
      (node (ref "LED2") (pin "A") (pinfunction "A_A") (pintype "passive"))
      (node (ref "R13") (pin "1") (pinfunction "1_1") (pintype "passive"))
    )
    (net (code "42") (name "Net-(LED3-PadA)") (class "Default")
      (node (ref "LED3") (pin "A") (pinfunction "A_A") (pintype "passive"))
      (node (ref "R14") (pin "1") (pinfunction "1_1") (pintype "passive"))
    )
    (net (code "43") (name "Net-(Q1-G)") (class "Default")
      (node (ref "Q1") (pin "1") (pinfunction "G_1") (pintype "passive"))
      (node (ref "R11") (pin "1") (pinfunction "1_1") (pintype "passive"))
      (node (ref "R20") (pin "2") (pinfunction "2_2") (pintype "passive"))
    )
    (net (code "44") (name "Net-(Q3-D)") (class "Default")
      (node (ref "Q3") (pin "3") (pinfunction "D_3") (pintype "passive"))
      (node (ref "VACUUM") (pin "3") (pinfunction "3_3") (pintype "bidirectional"))
    )
    (net (code "45") (name "Net-(Q3-G)") (class "Default")
      (node (ref "Q3") (pin "1") (pinfunction "G_1") (pintype "passive"))
      (node (ref "R19") (pin "2") (pinfunction "2_2") (pintype "passive"))
      (node (ref "R21") (pin "1") (pinfunction "1_1") (pintype "passive"))
    )
    (net (code "46") (name "Net-(Q4-D)") (class "Default")
      (node (ref "Q4") (pin "3") (pinfunction "D_3") (pintype "passive"))
      (node (ref "SPINDLE") (pin "3") (pinfunction "3_3") (pintype "bidirectional"))
    )
    (net (code "47") (name "Net-(Q4-G)") (class "Default")
      (node (ref "Q4") (pin "1") (pinfunction "G_1") (pintype "passive"))
      (node (ref "R23") (pin "2") (pinfunction "2_2") (pintype "passive"))
      (node (ref "R26") (pin "1") (pinfunction "1_1") (pintype "passive"))
    )
    (net (code "48") (name "Net-(Q7-G)") (class "Default")
      (node (ref "Q7") (pin "1") (pinfunction "G_1") (pintype "passive"))
      (node (ref "R1") (pin "1") (pinfunction "1_1") (pintype "passive"))
      (node (ref "R10") (pin "2") (pinfunction "2_2") (pintype "passive"))
    )
    (net (code "49") (name "Net-(Q8-G)") (class "Default")
      (node (ref "Q8") (pin "1") (pinfunction "G_1") (pintype "passive"))
      (node (ref "R16") (pin "2") (pinfunction "2_2") (pintype "passive"))
      (node (ref "R3") (pin "1") (pinfunction "1_1") (pintype "passive"))
    )
    (net (code "50") (name "Net-(Q9-G)") (class "Default")
      (node (ref "Q9") (pin "1") (pinfunction "G_1") (pintype "passive"))
      (node (ref "R17") (pin "2") (pinfunction "2_2") (pintype "passive"))
      (node (ref "R46") (pin "1") (pinfunction "1_1") (pintype "passive"))
    )
    (net (code "51") (name "Net-(Q10-G)") (class "Default")
      (node (ref "Q10") (pin "1") (pinfunction "G_1") (pintype "passive"))
      (node (ref "R22") (pin "2") (pinfunction "2_2") (pintype "passive"))
      (node (ref "R47") (pin "1") (pinfunction "1_1") (pintype "passive"))
    )
    (net (code "52") (name "Net-(Q11-G)") (class "Default")
      (node (ref "Q11") (pin "1") (pinfunction "G_1") (pintype "passive"))
      (node (ref "R24") (pin "2") (pinfunction "2_2") (pintype "passive"))
      (node (ref "R48") (pin "1") (pinfunction "1_1") (pintype "passive"))
    )
    (net (code "53") (name "Net-(Q12-G)") (class "Default")
      (node (ref "Q12") (pin "1") (pinfunction "G_1") (pintype "passive"))
      (node (ref "R25") (pin "2") (pinfunction "2_2") (pintype "passive"))
      (node (ref "R49") (pin "1") (pinfunction "1_1") (pintype "passive"))
    )
    (net (code "54") (name "Net-(Q13-G)") (class "Default")
      (node (ref "Q13") (pin "1") (pinfunction "G_1") (pintype "passive"))
      (node (ref "R29") (pin "2") (pinfunction "2_2") (pintype "passive"))
      (node (ref "R52") (pin "1") (pinfunction "1_1") (pintype "passive"))
    )
    (net (code "55") (name "Net-(Q14-G)") (class "Default")
      (node (ref "Q14") (pin "1") (pinfunction "G_1") (pintype "passive"))
      (node (ref "R30") (pin "2") (pinfunction "2_2") (pintype "passive"))
      (node (ref "R51") (pin "1") (pinfunction "1_1") (pintype "passive"))
    )
    (net (code "56") (name "Net-(Q15-G)") (class "Default")
      (node (ref "Q15") (pin "1") (pinfunction "G_1") (pintype "passive"))
      (node (ref "R31") (pin "2") (pinfunction "2_2") (pintype "passive"))
      (node (ref "R50") (pin "1") (pinfunction "1_1") (pintype "passive"))
    )
    (net (code "57") (name "Net-(Q16-G)") (class "Default")
      (node (ref "Q16") (pin "1") (pinfunction "G_1") (pintype "passive"))
      (node (ref "R37") (pin "2") (pinfunction "2_2") (pintype "passive"))
      (node (ref "R56") (pin "1") (pinfunction "1_1") (pintype "passive"))
    )
    (net (code "58") (name "Net-(Q17-G)") (class "Default")
      (node (ref "Q17") (pin "1") (pinfunction "G_1") (pintype "passive"))
      (node (ref "R38") (pin "2") (pinfunction "2_2") (pintype "passive"))
      (node (ref "R55") (pin "1") (pinfunction "1_1") (pintype "passive"))
    )
    (net (code "59") (name "Net-(Q18-G)") (class "Default")
      (node (ref "Q18") (pin "1") (pinfunction "G_1") (pintype "passive"))
      (node (ref "R39") (pin "2") (pinfunction "2_2") (pintype "passive"))
      (node (ref "R54") (pin "1") (pinfunction "1_1") (pintype "passive"))
    )
    (net (code "60") (name "Net-(Q19-G)") (class "Default")
      (node (ref "Q19") (pin "1") (pinfunction "G_1") (pintype "passive"))
      (node (ref "R43") (pin "2") (pinfunction "2_2") (pintype "passive"))
      (node (ref "R57") (pin "1") (pinfunction "1_1") (pintype "passive"))
    )
    (net (code "61") (name "Net-(Q20-G)") (class "Default")
      (node (ref "Q20") (pin "1") (pinfunction "G_1") (pintype "passive"))
      (node (ref "R44") (pin "2") (pinfunction "2_2") (pintype "passive"))
      (node (ref "R58") (pin "1") (pinfunction "1_1") (pintype "passive"))
    )
    (net (code "62") (name "Net-(Q21-G)") (class "Default")
      (node (ref "Q21") (pin "1") (pinfunction "G_1") (pintype "passive"))
      (node (ref "R45") (pin "2") (pinfunction "2_2") (pintype "passive"))
      (node (ref "R53") (pin "1") (pinfunction "1_1") (pintype "passive"))
    )
    (net (code "63") (name "Net-(S1-Pad3)") (class "Default")
      (node (ref "S1") (pin "3") (pinfunction "3_3") (pintype "passive"))
      (node (ref "S1") (pin "4") (pinfunction "4_4") (pintype "passive"))
      (node (ref "U$1") (pin "RESET") (pinfunction "RESET_RESET") (pintype "bidirectional"))
    )
    (net (code "64") (name "Net-(T1-G)") (class "Default")
      (node (ref "R32") (pin "2") (pinfunction "2_2") (pintype "passive"))
      (node (ref "R60") (pin "1") (pinfunction "1_1") (pintype "passive"))
      (node (ref "T1") (pin "1") (pinfunction "G_1") (pintype "passive"))
    )
    (net (code "65") (name "Net-(T2-G)") (class "Default")
      (node (ref "R4") (pin "2") (pinfunction "2_2") (pintype "passive"))
      (node (ref "R59") (pin "1") (pinfunction "1_1") (pintype "passive"))
      (node (ref "T2") (pin "1") (pinfunction "G_1") (pintype "passive"))
    )
    (net (code "66") (name "Net-(T3-G)") (class "Default")
      (node (ref "R5") (pin "2") (pinfunction "2_2") (pintype "passive"))
      (node (ref "R61") (pin "1") (pinfunction "1_1") (pintype "passive"))
      (node (ref "T3") (pin "1") (pinfunction "G_1") (pintype "passive"))
    )
    (net (code "67") (name "OK_PIN") (class "Default")
      (node (ref "C11") (pin "1") (pinfunction "1_1") (pintype "passive"))
      (node (ref "ENCODER") (pin "1") (pinfunction "1_1") (pintype "bidirectional"))
      (node (ref "R7") (pin "1") (pinfunction "1_1") (pintype "passive"))
      (node (ref "U$1") (pin "D24") (pinfunction "D24_D24") (pintype "bidirectional"))
    )
    (net (code "68") (name "RED") (class "Default")
      (node (ref "R60") (pin "2") (pinfunction "2_2") (pintype "passive"))
      (node (ref "U$1") (pin "D7") (pinfunction "D7_D7") (pintype "bidirectional"))
    )
    (net (code "69") (name "REDOUT") (class "Default")
      (node (ref "LEDS") (pin "3") (pinfunction "3_3") (pintype "bidirectional"))
      (node (ref "LEDS1") (pin "3") (pinfunction "3_3") (pintype "bidirectional"))
      (node (ref "T1") (pin "2") (pinfunction "D_2") (pintype "passive"))
    )
    (net (code "70") (name "RX0") (class "Default")
      (node (ref "U$1") (pin "D0") (pinfunction "D0_D0") (pintype "bidirectional"))
    )
    (net (code "71") (name "RX1") (class "Default")
      (node (ref "U$1") (pin "D19") (pinfunction "D19_D19") (pintype "bidirectional"))
      (node (ref "UART1") (pin "2") (pinfunction "2_2") (pintype "bidirectional"))
    )
    (net (code "72") (name "RX2") (class "Default")
      (node (ref "U$1") (pin "D17") (pinfunction "D17_D17") (pintype "bidirectional"))
      (node (ref "UART2") (pin "2") (pinfunction "2_2") (pintype "bidirectional"))
    )
    (net (code "73") (name "SCK") (class "Default")
      (node (ref "SPI") (pin "4") (pinfunction "4_4") (pintype "bidirectional"))
      (node (ref "U$1") (pin "D52") (pinfunction "D52_D52") (pintype "bidirectional"))
      (node (ref "U16") (pin "5") (pinfunction "SCK_5") (pintype "bidirectional"))
    )
    (net (code "74") (name "SCL") (class "Default")
      (node (ref "I2C") (pin "2") (pinfunction "2_2") (pintype "bidirectional"))
      (node (ref "U$1") (pin "D21") (pinfunction "D21_D21") (pintype "bidirectional"))
    )
    (net (code "75") (name "SDA") (class "Default")
      (node (ref "I2C") (pin "3") (pinfunction "3_3") (pintype "bidirectional"))
      (node (ref "U$1") (pin "D20") (pinfunction "D20_D20") (pintype "bidirectional"))
    )
    (net (code "76") (name "SD_SELECT") (class "Default")
      (node (ref "U$1") (pin "D49") (pinfunction "D49_D49") (pintype "bidirectional"))
      (node (ref "U16") (pin "2") (pinfunction "CS_2") (pintype "bidirectional"))
    )
    (net (code "77") (name "SPINDLE") (class "Default")
      (node (ref "R26") (pin "2") (pinfunction "2_2") (pintype "passive"))
      (node (ref "U$1") (pin "D4") (pinfunction "D4_D4") (pintype "bidirectional"))
    )
    (net (code "78") (name "SS") (class "Default")
      (node (ref "SPI") (pin "5") (pinfunction "5_5") (pintype "bidirectional"))
      (node (ref "U$1") (pin "D53") (pinfunction "D53_D53") (pintype "bidirectional"))
    )
    (net (code "79") (name "TACHOMETER") (class "Default")
      (node (ref "C1") (pin "2") (pinfunction "2_2") (pintype "passive"))
      (node (ref "TACH") (pin "3") (pinfunction "3_3") (pintype "bidirectional"))
      (node (ref "U$1") (pin "D2") (pinfunction "D2_D2") (pintype "bidirectional"))
    )
    (net (code "80") (name "TOOLZERO") (class "Default")
      (node (ref "C9") (pin "2") (pinfunction "2_2") (pintype "passive"))
      (node (ref "TOOLZERO") (pin "3") (pinfunction "3_3") (pintype "bidirectional"))
      (node (ref "U$1") (pin "D26") (pinfunction "D26_D26") (pintype "bidirectional"))
    )
    (net (code "81") (name "TX0") (class "Default")
      (node (ref "U$1") (pin "D1") (pinfunction "D1_D1") (pintype "bidirectional"))
    )
    (net (code "82") (name "TX1") (class "Default")
      (node (ref "U$1") (pin "D18") (pinfunction "D18_D18") (pintype "bidirectional"))
      (node (ref "UART1") (pin "3") (pinfunction "3_3") (pintype "bidirectional"))
    )
    (net (code "83") (name "TX2") (class "Default")
      (node (ref "U$1") (pin "D16") (pinfunction "D16_D16") (pintype "bidirectional"))
      (node (ref "UART2") (pin "3") (pinfunction "3_3") (pintype "bidirectional"))
    )
    (net (code "84") (name "VACUUM") (class "Default")
      (node (ref "R21") (pin "2") (pinfunction "2_2") (pintype "passive"))
      (node (ref "U$1") (pin "D3") (pinfunction "D3_D3") (pintype "bidirectional"))
    )
    (net (code "85") (name "VCC") (class "Default")
      (node (ref "DOOR") (pin "1") (pinfunction "1_1") (pintype "bidirectional"))
      (node (ref "I2C") (pin "1") (pinfunction "1_1") (pintype "bidirectional"))
      (node (ref "JP1") (pin "2") (pinfunction "2_2") (pintype "passive"))
      (node (ref "LCD") (pin "15") (pinfunction "15_15") (pintype "bidirectional"))
      (node (ref "LCD") (pin "2") (pinfunction "2_2") (pintype "bidirectional"))
      (node (ref "R15") (pin "2") (pinfunction "2_2") (pintype "passive"))
      (node (ref "R6") (pin "E") (pinfunction "E_E") (pintype "passive"))
      (node (ref "R7") (pin "2") (pinfunction "2_2") (pintype "passive"))
      (node (ref "R8") (pin "2") (pinfunction "2_2") (pintype "passive"))
      (node (ref "SPI") (pin "1") (pinfunction "1_1") (pintype "bidirectional"))
      (node (ref "SPINDLE") (pin "1") (pinfunction "1_1") (pintype "bidirectional"))
      (node (ref "TACH") (pin "1") (pinfunction "1_1") (pintype "bidirectional"))
      (node (ref "TOOLZERO") (pin "1") (pinfunction "1_1") (pintype "bidirectional"))
      (node (ref "U16") (pin "4") (pinfunction "VCC_4") (pintype "bidirectional"))
      (node (ref "UART1") (pin "1") (pinfunction "1_1") (pintype "bidirectional"))
      (node (ref "UART2") (pin "1") (pinfunction "1_1") (pintype "bidirectional"))
      (node (ref "VACUUM") (pin "1") (pinfunction "1_1") (pintype "bidirectional"))
      (node (ref "XMAX") (pin "1") (pinfunction "1_1") (pintype "bidirectional"))
      (node (ref "XMIN") (pin "1") (pinfunction "1_1") (pintype "bidirectional"))
      (node (ref "YMAX") (pin "1") (pinfunction "1_1") (pintype "bidirectional"))
      (node (ref "YMIN") (pin "1") (pinfunction "1_1") (pintype "bidirectional"))
      (node (ref "ZMAX") (pin "1") (pinfunction "1_1") (pintype "bidirectional"))
      (node (ref "ZMIN") (pin "1") (pinfunction "1_1") (pintype "bidirectional"))
    )
    (net (code "86") (name "XDIR") (class "Default")
      (node (ref "R3") (pin "2") (pinfunction "2_2") (pintype "passive"))
      (node (ref "U$1") (pin "D34") (pinfunction "D34_D34") (pintype "bidirectional"))
    )
    (net (code "87") (name "XDIROUT") (class "Default")
      (node (ref "Q8") (pin "3") (pinfunction "D_3") (pintype "passive"))
      (node (ref "X") (pin "4") (pinfunction "4_4") (pintype "bidirectional"))
    )
    (net (code "88") (name "XENABLE") (class "Default")
      (node (ref "R46") (pin "2") (pinfunction "2_2") (pintype "passive"))
      (node (ref "U$1") (pin "D35") (pinfunction "D35_D35") (pintype "bidirectional"))
    )
    (net (code "89") (name "XENABLEOUT") (class "Default")
      (node (ref "Q9") (pin "3") (pinfunction "D_3") (pintype "passive"))
      (node (ref "X") (pin "6") (pinfunction "6_6") (pintype "bidirectional"))
    )
    (net (code "90") (name "XMAX") (class "Default")
      (node (ref "C5") (pin "2") (pinfunction "2_2") (pintype "passive"))
      (node (ref "U$1") (pin "D28") (pinfunction "D28_D28") (pintype "bidirectional"))
      (node (ref "XMAX") (pin "3") (pinfunction "3_3") (pintype "bidirectional"))
    )
    (net (code "91") (name "XMIN") (class "Default")
      (node (ref "C6") (pin "2") (pinfunction "2_2") (pintype "passive"))
      (node (ref "U$1") (pin "D27") (pinfunction "D27_D27") (pintype "bidirectional"))
      (node (ref "XMIN") (pin "3") (pinfunction "3_3") (pintype "bidirectional"))
    )
    (net (code "92") (name "XSTEP") (class "Default")
      (node (ref "R1") (pin "2") (pinfunction "2_2") (pintype "passive"))
      (node (ref "U$1") (pin "D33") (pinfunction "D33_D33") (pintype "bidirectional"))
    )
    (net (code "93") (name "XSTEPOUT") (class "Default")
      (node (ref "Q7") (pin "3") (pinfunction "D_3") (pintype "passive"))
      (node (ref "X") (pin "2") (pinfunction "2_2") (pintype "bidirectional"))
    )
    (net (code "94") (name "YDIR") (class "Default")
      (node (ref "R48") (pin "2") (pinfunction "2_2") (pintype "passive"))
      (node (ref "U$1") (pin "D37") (pinfunction "D37_D37") (pintype "bidirectional"))
    )
    (net (code "95") (name "YDIROUT") (class "Default")
      (node (ref "Q11") (pin "3") (pinfunction "D_3") (pintype "passive"))
      (node (ref "Y") (pin "4") (pinfunction "4_4") (pintype "bidirectional"))
    )
    (net (code "96") (name "YENABLE") (class "Default")
      (node (ref "R49") (pin "2") (pinfunction "2_2") (pintype "passive"))
      (node (ref "U$1") (pin "D38") (pinfunction "D38_D38") (pintype "bidirectional"))
    )
    (net (code "97") (name "YENABLEOUT") (class "Default")
      (node (ref "Q12") (pin "3") (pinfunction "D_3") (pintype "passive"))
      (node (ref "Y") (pin "6") (pinfunction "6_6") (pintype "bidirectional"))
    )
    (net (code "98") (name "YMAX") (class "Default")
      (node (ref "C4") (pin "2") (pinfunction "2_2") (pintype "passive"))
      (node (ref "U$1") (pin "D30") (pinfunction "D30_D30") (pintype "bidirectional"))
      (node (ref "YMAX") (pin "3") (pinfunction "3_3") (pintype "bidirectional"))
    )
    (net (code "99") (name "YMIN") (class "Default")
      (node (ref "C7") (pin "2") (pinfunction "2_2") (pintype "passive"))
      (node (ref "U$1") (pin "D29") (pinfunction "D29_D29") (pintype "bidirectional"))
      (node (ref "YMIN") (pin "3") (pinfunction "3_3") (pintype "bidirectional"))
    )
    (net (code "100") (name "YSTEP") (class "Default")
      (node (ref "R47") (pin "2") (pinfunction "2_2") (pintype "passive"))
      (node (ref "U$1") (pin "D36") (pinfunction "D36_D36") (pintype "bidirectional"))
    )
    (net (code "101") (name "YSTEPOUT") (class "Default")
      (node (ref "Q10") (pin "3") (pinfunction "D_3") (pintype "passive"))
      (node (ref "Y") (pin "2") (pinfunction "2_2") (pintype "bidirectional"))
    )
    (net (code "102") (name "ZDIR") (class "Default")
      (node (ref "R51") (pin "2") (pinfunction "2_2") (pintype "passive"))
      (node (ref "U$1") (pin "D40") (pinfunction "D40_D40") (pintype "bidirectional"))
    )
    (net (code "103") (name "ZDIROUT") (class "Default")
      (node (ref "Q14") (pin "3") (pinfunction "D_3") (pintype "passive"))
      (node (ref "Z") (pin "4") (pinfunction "4_4") (pintype "bidirectional"))
    )
    (net (code "104") (name "ZENABLE") (class "Default")
      (node (ref "R50") (pin "2") (pinfunction "2_2") (pintype "passive"))
      (node (ref "U$1") (pin "D41") (pinfunction "D41_D41") (pintype "bidirectional"))
    )
    (net (code "105") (name "ZENABLEOUT") (class "Default")
      (node (ref "Q15") (pin "3") (pinfunction "D_3") (pintype "passive"))
      (node (ref "Z") (pin "6") (pinfunction "6_6") (pintype "bidirectional"))
    )
    (net (code "106") (name "ZMAX") (class "Default")
      (node (ref "C3") (pin "2") (pinfunction "2_2") (pintype "passive"))
      (node (ref "U$1") (pin "D32") (pinfunction "D32_D32") (pintype "bidirectional"))
      (node (ref "ZMAX") (pin "3") (pinfunction "3_3") (pintype "bidirectional"))
    )
    (net (code "107") (name "ZMIN") (class "Default")
      (node (ref "C8") (pin "2") (pinfunction "2_2") (pintype "passive"))
      (node (ref "U$1") (pin "D31") (pinfunction "D31_D31") (pintype "bidirectional"))
      (node (ref "ZMIN") (pin "3") (pinfunction "3_3") (pintype "bidirectional"))
    )
    (net (code "108") (name "ZSTEP") (class "Default")
      (node (ref "R52") (pin "2") (pinfunction "2_2") (pintype "passive"))
      (node (ref "U$1") (pin "D39") (pinfunction "D39_D39") (pintype "bidirectional"))
    )
    (net (code "109") (name "ZSTEPOUT") (class "Default")
      (node (ref "Q13") (pin "3") (pinfunction "D_3") (pintype "passive"))
      (node (ref "Z") (pin "2") (pinfunction "2_2") (pintype "bidirectional"))
    )
    (net (code "110") (name "unconnected-(LCD-Pad7)") (class "Default")
      (node (ref "LCD") (pin "7") (pinfunction "7_7") (pintype "bidirectional"))
    )
    (net (code "111") (name "unconnected-(LCD-Pad8)") (class "Default")
      (node (ref "LCD") (pin "8") (pinfunction "8_8") (pintype "bidirectional"))
    )
    (net (code "112") (name "unconnected-(LCD-Pad9)") (class "Default")
      (node (ref "LCD") (pin "9") (pinfunction "9_9") (pintype "bidirectional"))
    )
    (net (code "113") (name "unconnected-(LCD-Pad10)") (class "Default")
      (node (ref "LCD") (pin "10") (pinfunction "10_10") (pintype "bidirectional"))
    )
    (net (code "114") (name "unconnected-(U$1-5V1-Pad5V-2)") (class "Default")
      (node (ref "U$1") (pin "5V-2") (pinfunction "5V1_5V-2") (pintype "bidirectional"))
    )
    (net (code "115") (name "unconnected-(U$1-Pad5V)") (class "Default")
      (node (ref "U$1") (pin "5V") (pinfunction "5V_5V") (pintype "bidirectional"))
    )
    (net (code "116") (name "unconnected-(U$1-PadA0)") (class "Default")
      (node (ref "U$1") (pin "A0") (pinfunction "A0_A0") (pintype "bidirectional"))
    )
    (net (code "117") (name "unconnected-(U$1-PadA1)") (class "Default")
      (node (ref "U$1") (pin "A1") (pinfunction "A1_A1") (pintype "bidirectional"))
    )
    (net (code "118") (name "unconnected-(U$1-PadA2)") (class "Default")
      (node (ref "U$1") (pin "A2") (pinfunction "A2_A2") (pintype "bidirectional"))
    )
    (net (code "119") (name "unconnected-(U$1-PadA3)") (class "Default")
      (node (ref "U$1") (pin "A3") (pinfunction "A3_A3") (pintype "bidirectional"))
    )
    (net (code "120") (name "unconnected-(U$1-PadA4)") (class "Default")
      (node (ref "U$1") (pin "A4") (pinfunction "A4_A4") (pintype "bidirectional"))
    )
    (net (code "121") (name "unconnected-(U$1-PadA5)") (class "Default")
      (node (ref "U$1") (pin "A5") (pinfunction "A5_A5") (pintype "bidirectional"))
    )
    (net (code "122") (name "unconnected-(U$1-PadA6)") (class "Default")
      (node (ref "U$1") (pin "A6") (pinfunction "A6_A6") (pintype "bidirectional"))
    )
    (net (code "123") (name "unconnected-(U$1-PadA7)") (class "Default")
      (node (ref "U$1") (pin "A7") (pinfunction "A7_A7") (pintype "bidirectional"))
    )
    (net (code "124") (name "unconnected-(U$1-PadA8)") (class "Default")
      (node (ref "U$1") (pin "A8") (pinfunction "A8_A8") (pintype "bidirectional"))
    )
    (net (code "125") (name "unconnected-(U$1-PadA9)") (class "Default")
      (node (ref "U$1") (pin "A9") (pinfunction "A9_A9") (pintype "bidirectional"))
    )
    (net (code "126") (name "unconnected-(U$1-PadA10)") (class "Default")
      (node (ref "U$1") (pin "A10") (pinfunction "A10_A10") (pintype "bidirectional"))
    )
    (net (code "127") (name "unconnected-(U$1-PadA11)") (class "Default")
      (node (ref "U$1") (pin "A11") (pinfunction "A11_A11") (pintype "bidirectional"))
    )
    (net (code "128") (name "unconnected-(U$1-PadA12)") (class "Default")
      (node (ref "U$1") (pin "A12") (pinfunction "A12_A12") (pintype "bidirectional"))
    )
    (net (code "129") (name "unconnected-(U$1-PadA13)") (class "Default")
      (node (ref "U$1") (pin "A13") (pinfunction "A13_A13") (pintype "bidirectional"))
    )
    (net (code "130") (name "unconnected-(U$1-PadA14)") (class "Default")
      (node (ref "U$1") (pin "A14") (pinfunction "A14_A14") (pintype "bidirectional"))
    )
    (net (code "131") (name "unconnected-(U$1-PadA15)") (class "Default")
      (node (ref "U$1") (pin "A15") (pinfunction "A15_A15") (pintype "bidirectional"))
    )
    (net (code "132") (name "unconnected-(U$1-PadAREF)") (class "Default")
      (node (ref "U$1") (pin "AREF") (pinfunction "AREF_AREF") (pintype "bidirectional"))
    )
    (net (code "133") (name "unconnected-(U16-NC-Pad1)") (class "Default")
      (node (ref "U16") (pin "1") (pinfunction "NC_1") (pintype "bidirectional"))
    )
    (net (code "134") (name "unconnected-(U16-RSV-Pad8)") (class "Default")
      (node (ref "U16") (pin "8") (pinfunction "RSV_8") (pintype "bidirectional"))
    )
  )
)
